# board1.net
KiCad netlist of a schematic drawn in EAGLE
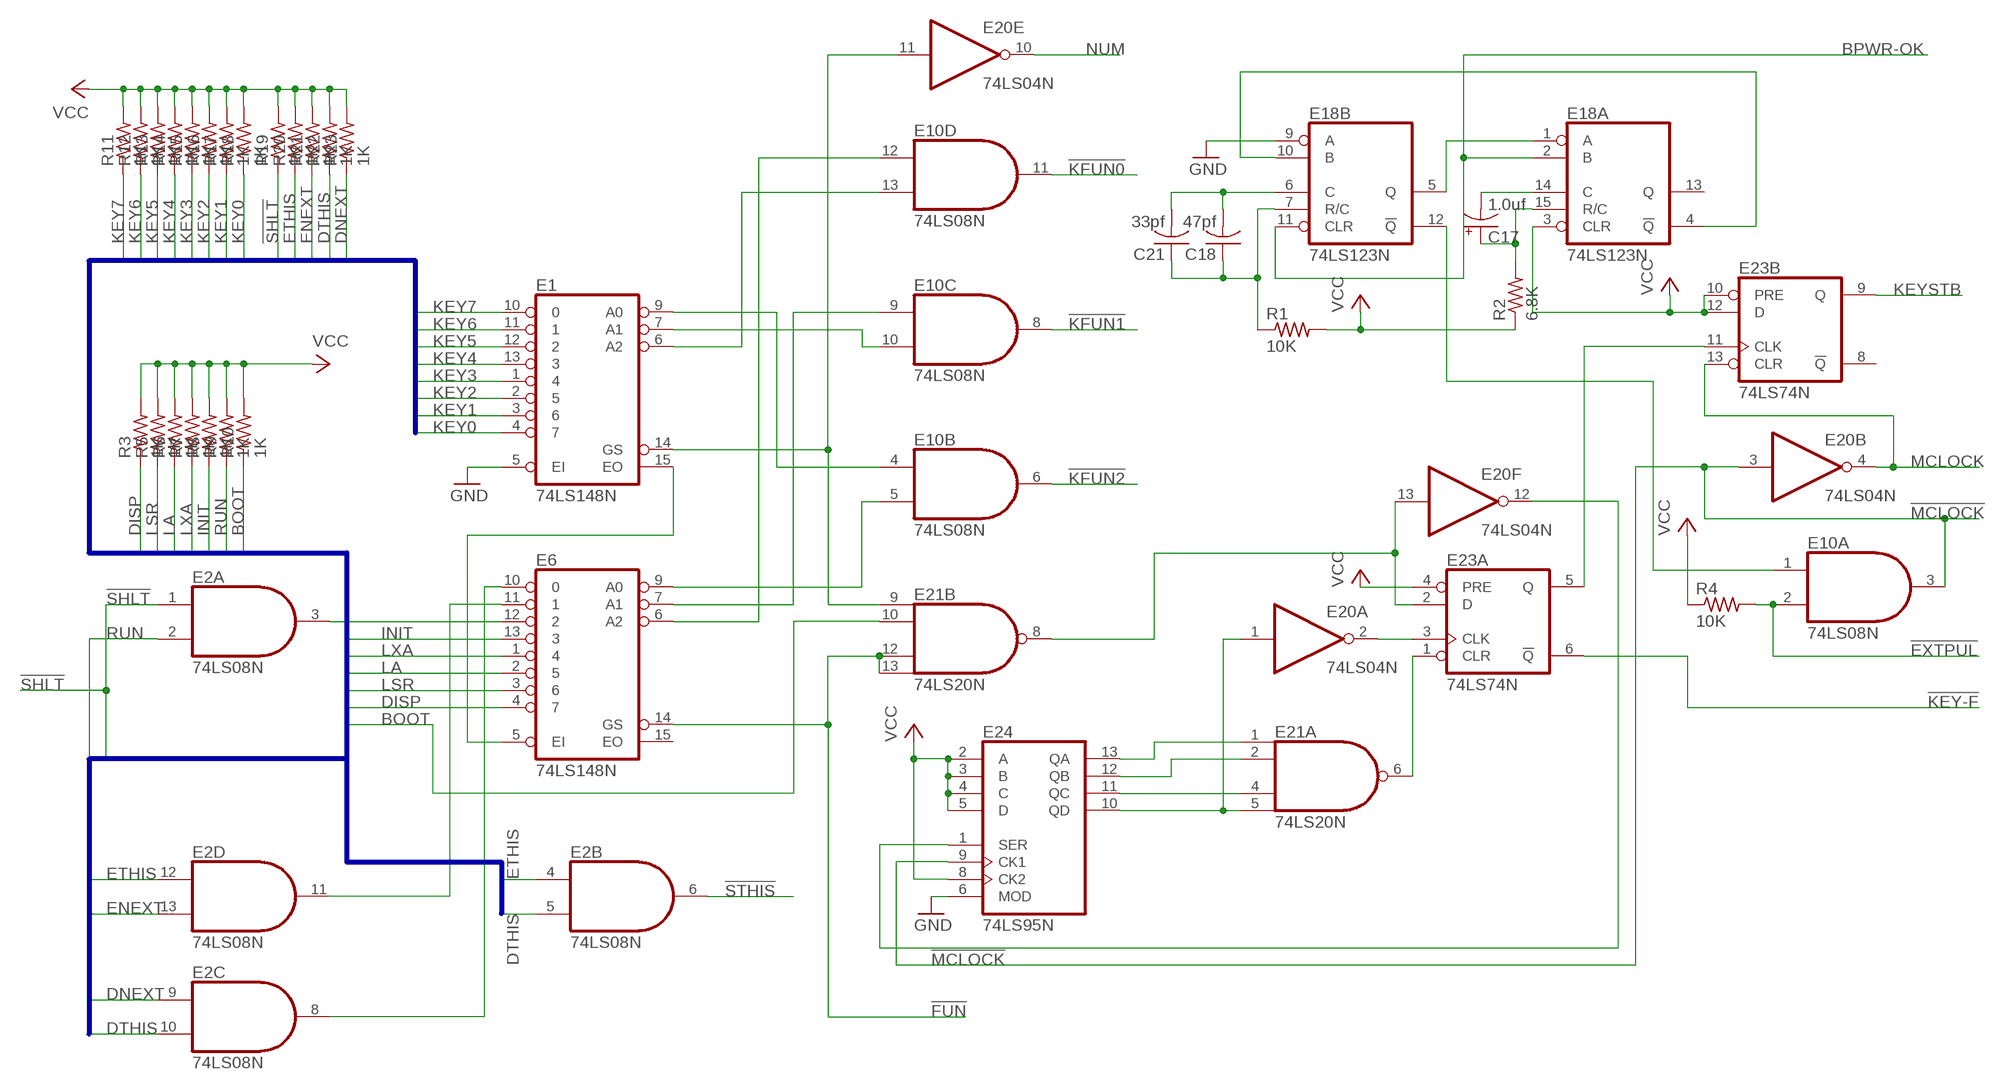
[diagram p0: schematic, sheet 1]
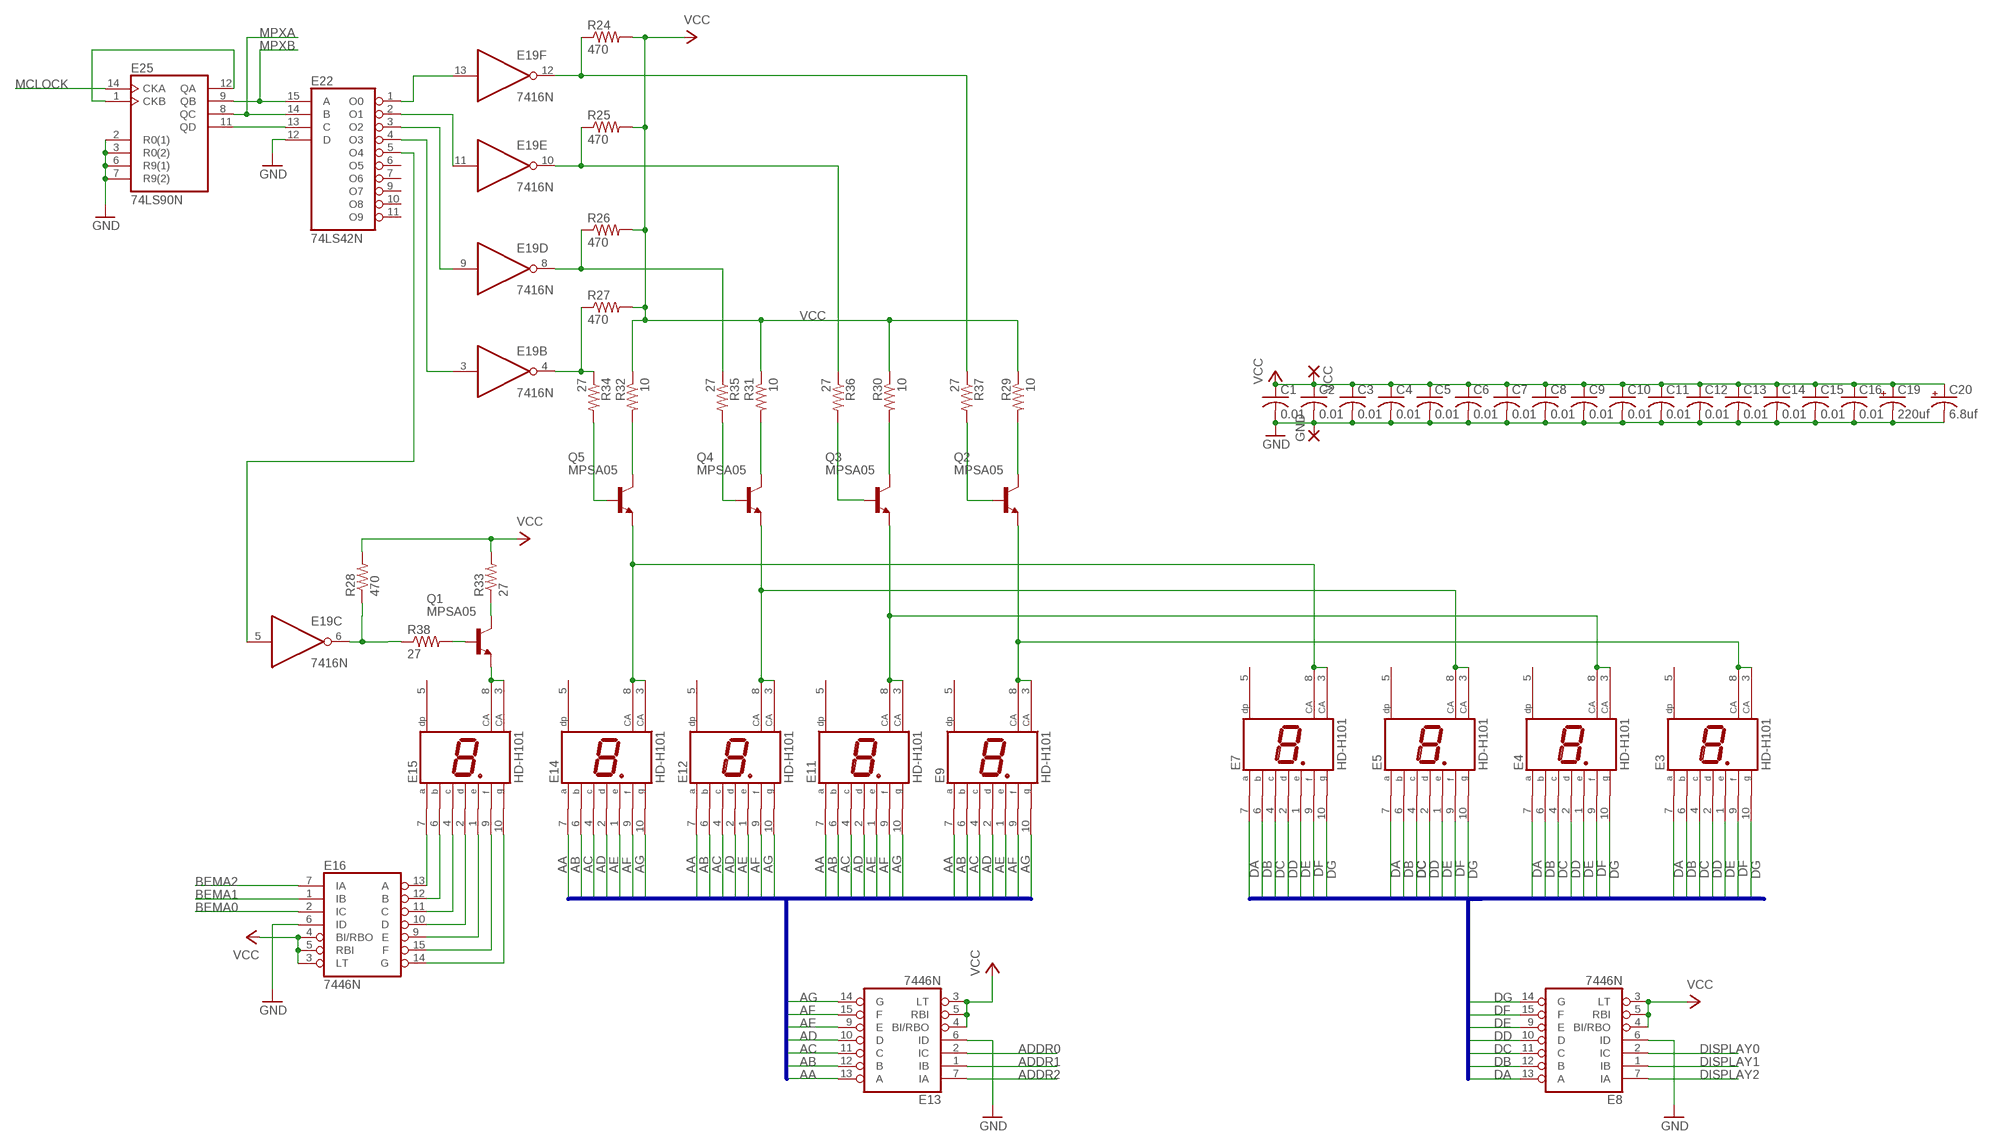
[diagram p1: schematic, sheet 2]
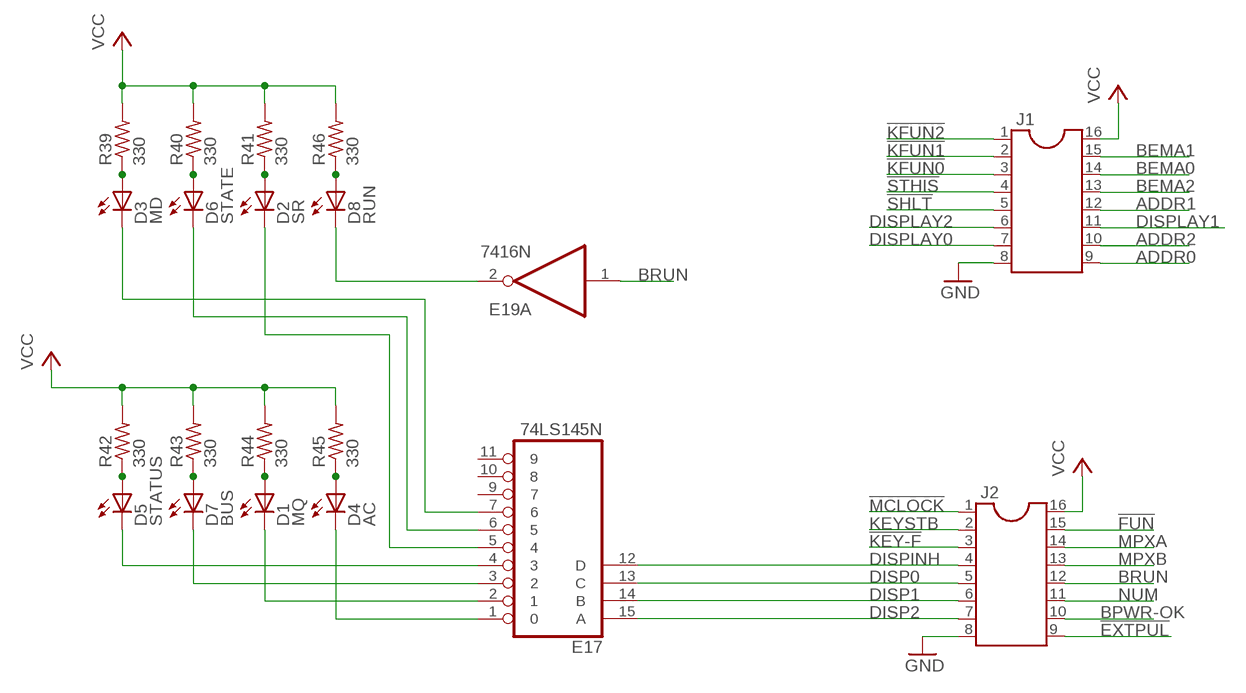
[diagram p2: schematic, sheet 3]
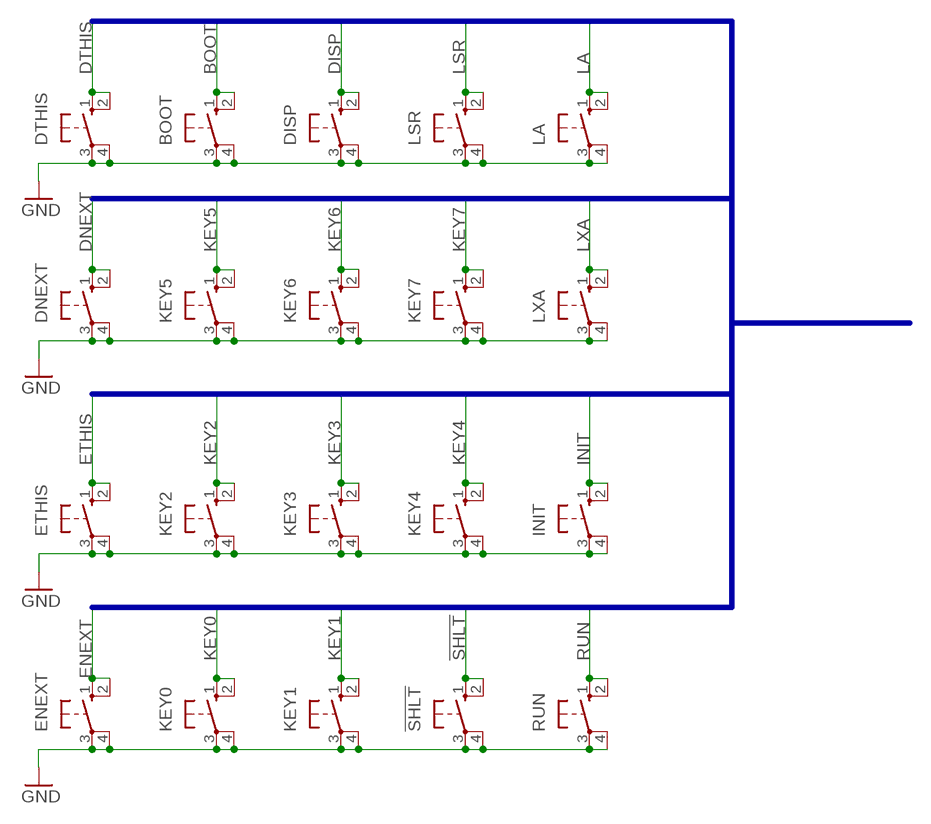
[diagram p3: schematic, sheet 4]

(export (version "E")
  (design (tool "Eeschema 10.0.6"))
  (components
    (comp (ref "C17")
      (value "1.0uf")
      (footprint "eagle-import:E15-5")
      (libsource (lib "eagle-import") (part "CPOL-USE15-5AXIAL"))
    )
    (comp (ref "C18")
      (value "47pf")
      (footprint "eagle-import:C050-025X075")
      (libsource (lib "eagle-import") (part "C-US050-025X075"))
    )
    (comp (ref "C21")
      (value "33pf")
      (footprint "eagle-import:C050-025X075")
      (libsource (lib "eagle-import") (part "C-US050-025X075"))
    )
    (comp (ref "E1")
      (value "74LS148N")
      (footprint "eagle-import:DIL16")
      (libsource (lib "eagle-import") (part "74148NLS"))
    )
    (comp (ref "E2")
      (value "74LS08N")
      (footprint "eagle-import:DIL14")
      (libsource (lib "eagle-import") (part "7408NLS"))
    )
    (comp (ref "E6")
      (value "74LS148N")
      (footprint "eagle-import:DIL16")
      (libsource (lib "eagle-import") (part "74148NLS"))
    )
    (comp (ref "E10")
      (value "74LS08N")
      (footprint "eagle-import:DIL14")
      (libsource (lib "eagle-import") (part "7408NLS"))
    )
    (comp (ref "E18")
      (value "74LS123N")
      (footprint "eagle-import:DIL16")
      (libsource (lib "eagle-import") (part "74123NLS"))
    )
    (comp (ref "E20")
      (value "74LS04N")
      (footprint "eagle-import:DIL14")
      (libsource (lib "eagle-import") (part "7404NLS"))
    )
    (comp (ref "E21")
      (value "74LS20N")
      (footprint "eagle-import:DIL14")
      (libsource (lib "eagle-import") (part "7420NLS"))
    )
    (comp (ref "E23")
      (value "74LS74N")
      (footprint "eagle-import:DIL14")
      (libsource (lib "eagle-import") (part "7474NLS"))
    )
    (comp (ref "E24")
      (value "74LS95N")
      (footprint "eagle-import:DIL14")
      (libsource (lib "eagle-import") (part "7495NLS"))
    )
    (comp (ref "R1")
      (value "10K")
      (footprint "eagle-import:0207_10")
      (libsource (lib "eagle-import") (part "R-US_0207/10"))
    )
    (comp (ref "R2")
      (value "6.8K")
      (footprint "eagle-import:0207_10")
      (libsource (lib "eagle-import") (part "R-US_0207/10"))
    )
    (comp (ref "R3")
      (value "1K")
      (footprint "eagle-import:0207_10")
      (libsource (lib "eagle-import") (part "R-US_0207/10"))
    )
    (comp (ref "R4")
      (value "10K")
      (footprint "eagle-import:0207_10")
      (libsource (lib "eagle-import") (part "R-US_0207/10"))
    )
    (comp (ref "R5")
      (value "1K")
      (footprint "eagle-import:0207_10")
      (libsource (lib "eagle-import") (part "R-US_0207/10"))
    )
    (comp (ref "R6")
      (value "1K")
      (footprint "eagle-import:0207_10")
      (libsource (lib "eagle-import") (part "R-US_0207/10"))
    )
    (comp (ref "R7")
      (value "1K")
      (footprint "eagle-import:0207_10")
      (libsource (lib "eagle-import") (part "R-US_0207/10"))
    )
    (comp (ref "R8")
      (value "1K")
      (footprint "eagle-import:0207_10")
      (libsource (lib "eagle-import") (part "R-US_0207/10"))
    )
    (comp (ref "R9")
      (value "1K")
      (footprint "eagle-import:0207_10")
      (libsource (lib "eagle-import") (part "R-US_0207/10"))
    )
    (comp (ref "R10")
      (value "1K")
      (footprint "eagle-import:0207_10")
      (libsource (lib "eagle-import") (part "R-US_0207/10"))
    )
    (comp (ref "R11")
      (value "1K")
      (footprint "eagle-import:0207_10")
      (libsource (lib "eagle-import") (part "R-US_0207/10"))
    )
    (comp (ref "R12")
      (value "1K")
      (footprint "eagle-import:0207_10")
      (libsource (lib "eagle-import") (part "R-US_0207/10"))
    )
    (comp (ref "R13")
      (value "1K")
      (footprint "eagle-import:0207_10")
      (libsource (lib "eagle-import") (part "R-US_0207/10"))
    )
    (comp (ref "R14")
      (value "1K")
      (footprint "eagle-import:0207_10")
      (libsource (lib "eagle-import") (part "R-US_0207/10"))
    )
    (comp (ref "R15")
      (value "1K")
      (footprint "eagle-import:0207_10")
      (libsource (lib "eagle-import") (part "R-US_0207/10"))
    )
    (comp (ref "R16")
      (value "1K")
      (footprint "eagle-import:0207_10")
      (libsource (lib "eagle-import") (part "R-US_0207/10"))
    )
    (comp (ref "R17")
      (value "1K")
      (footprint "eagle-import:0207_10")
      (libsource (lib "eagle-import") (part "R-US_0207/10"))
    )
    (comp (ref "R18")
      (value "1K")
      (footprint "eagle-import:0207_10")
      (libsource (lib "eagle-import") (part "R-US_0207/10"))
    )
    (comp (ref "R19")
      (value "1K")
      (footprint "eagle-import:0207_10")
      (libsource (lib "eagle-import") (part "R-US_0207/10"))
    )
    (comp (ref "R20")
      (value "1K")
      (footprint "eagle-import:0207_10")
      (libsource (lib "eagle-import") (part "R-US_0207/10"))
    )
    (comp (ref "R21")
      (value "1K")
      (footprint "eagle-import:0207_10")
      (libsource (lib "eagle-import") (part "R-US_0207/10"))
    )
    (comp (ref "R22")
      (value "1K")
      (footprint "eagle-import:0207_10")
      (libsource (lib "eagle-import") (part "R-US_0207/10"))
    )
    (comp (ref "R23")
      (value "1K")
      (footprint "eagle-import:0207_10")
      (libsource (lib "eagle-import") (part "R-US_0207/10"))
    )
    (comp (ref "C1")
      (value "0.01")
      (footprint "eagle-import:C050-025X075")
      (libsource (lib "eagle-import") (part "C-US050-025X075"))
    )
    (comp (ref "C2")
      (value "0.01")
      (footprint "eagle-import:C050-025X075")
      (libsource (lib "eagle-import") (part "C-US050-025X075"))
    )
    (comp (ref "C3")
      (value "0.01")
      (footprint "eagle-import:C050-025X075")
      (libsource (lib "eagle-import") (part "C-US050-025X075"))
    )
    (comp (ref "C4")
      (value "0.01")
      (footprint "eagle-import:C050-025X075")
      (libsource (lib "eagle-import") (part "C-US050-025X075"))
    )
    (comp (ref "C5")
      (value "0.01")
      (footprint "eagle-import:C050-025X075")
      (libsource (lib "eagle-import") (part "C-US050-025X075"))
    )
    (comp (ref "C6")
      (value "0.01")
      (footprint "eagle-import:C050-025X075")
      (libsource (lib "eagle-import") (part "C-US050-025X075"))
    )
    (comp (ref "C7")
      (value "0.01")
      (footprint "eagle-import:C050-025X075")
      (libsource (lib "eagle-import") (part "C-US050-025X075"))
    )
    (comp (ref "C8")
      (value "0.01")
      (footprint "eagle-import:C050-025X075")
      (libsource (lib "eagle-import") (part "C-US050-025X075"))
    )
    (comp (ref "C9")
      (value "0.01")
      (footprint "eagle-import:C050-025X075")
      (libsource (lib "eagle-import") (part "C-US050-025X075"))
    )
    (comp (ref "C10")
      (value "0.01")
      (footprint "eagle-import:C050-025X075")
      (libsource (lib "eagle-import") (part "C-US050-025X075"))
    )
    (comp (ref "C11")
      (value "0.01")
      (footprint "eagle-import:C050-025X075")
      (libsource (lib "eagle-import") (part "C-US050-025X075"))
    )
    (comp (ref "C12")
      (value "0.01")
      (footprint "eagle-import:C050-025X075")
      (libsource (lib "eagle-import") (part "C-US050-025X075"))
    )
    (comp (ref "C13")
      (value "0.01")
      (footprint "eagle-import:C050-025X075")
      (libsource (lib "eagle-import") (part "C-US050-025X075"))
    )
    (comp (ref "C14")
      (value "0.01")
      (footprint "eagle-import:C050-025X075")
      (libsource (lib "eagle-import") (part "C-US050-025X075"))
    )
    (comp (ref "C15")
      (value "0.01")
      (footprint "eagle-import:C050-025X075")
      (libsource (lib "eagle-import") (part "C-US050-025X075"))
    )
    (comp (ref "C16")
      (value "0.01")
      (footprint "eagle-import:C050-025X075")
      (libsource (lib "eagle-import") (part "C-US050-025X075"))
    )
    (comp (ref "C19")
      (value "220uf")
      (footprint "eagle-import:E22-6")
      (libsource (lib "eagle-import") (part "CPOL-USE22-6AXIAL"))
    )
    (comp (ref "C20")
      (value "6.8uf")
      (footprint "eagle-import:E22-6")
      (libsource (lib "eagle-import") (part "CPOL-USE22-6AXIAL"))
    )
    (comp (ref "E3")
      (value "HD-H101")
      (footprint "eagle-import:HDSP-M")
      (libsource (lib "eagle-import") (part "HD-H101"))
    )
    (comp (ref "E4")
      (value "HD-H101")
      (footprint "eagle-import:HDSP-M")
      (libsource (lib "eagle-import") (part "HD-H101"))
    )
    (comp (ref "E5")
      (value "HD-H101")
      (footprint "eagle-import:HDSP-M")
      (libsource (lib "eagle-import") (part "HD-H101"))
    )
    (comp (ref "E7")
      (value "HD-H101")
      (footprint "eagle-import:HDSP-M")
      (libsource (lib "eagle-import") (part "HD-H101"))
    )
    (comp (ref "E8")
      (value "7446N")
      (footprint "eagle-import:DIL16")
      (libsource (lib "eagle-import") (part "7446N"))
    )
    (comp (ref "E9")
      (value "HD-H101")
      (footprint "eagle-import:HDSP-M")
      (libsource (lib "eagle-import") (part "HD-H101"))
    )
    (comp (ref "E11")
      (value "HD-H101")
      (footprint "eagle-import:HDSP-M")
      (libsource (lib "eagle-import") (part "HD-H101"))
    )
    (comp (ref "E12")
      (value "HD-H101")
      (footprint "eagle-import:HDSP-M")
      (libsource (lib "eagle-import") (part "HD-H101"))
    )
    (comp (ref "E13")
      (value "7446N")
      (footprint "eagle-import:DIL16")
      (libsource (lib "eagle-import") (part "7446N"))
    )
    (comp (ref "E14")
      (value "HD-H101")
      (footprint "eagle-import:HDSP-M")
      (libsource (lib "eagle-import") (part "HD-H101"))
    )
    (comp (ref "E15")
      (value "HD-H101")
      (footprint "eagle-import:HDSP-M")
      (libsource (lib "eagle-import") (part "HD-H101"))
    )
    (comp (ref "E16")
      (value "7446N")
      (footprint "eagle-import:DIL16")
      (libsource (lib "eagle-import") (part "7446N"))
    )
    (comp (ref "E19")
      (value "7416N")
      (footprint "eagle-import:DIL14")
      (libsource (lib "eagle-import") (part "7416N"))
    )
    (comp (ref "E22")
      (value "74LS42N")
      (footprint "eagle-import:DIL16")
      (libsource (lib "eagle-import") (part "7442NLS"))
    )
    (comp (ref "E25")
      (value "74LS90N")
      (footprint "eagle-import:DIL14")
      (libsource (lib "eagle-import") (part "7490NLS"))
    )
    (comp (ref "GND")
      (value "3,81/1,4")
      (footprint "eagle-import:3,81_1,4")
      (libsource (lib "eagle-import") (part "3,81/1,4"))
    )
    (comp (ref "Q1")
      (value "MPSA05")
      (footprint "eagle-import:TO18")
      (libsource (lib "eagle-import") (part "2N2222A"))
    )
    (comp (ref "Q2")
      (value "MPSA05")
      (footprint "eagle-import:TO18")
      (libsource (lib "eagle-import") (part "2N2222A"))
    )
    (comp (ref "Q3")
      (value "MPSA05")
      (footprint "eagle-import:TO18")
      (libsource (lib "eagle-import") (part "2N2222A"))
    )
    (comp (ref "Q4")
      (value "MPSA05")
      (footprint "eagle-import:TO18")
      (libsource (lib "eagle-import") (part "2N2222A"))
    )
    (comp (ref "Q5")
      (value "MPSA05")
      (footprint "eagle-import:TO18")
      (libsource (lib "eagle-import") (part "2N2222A"))
    )
    (comp (ref "R24")
      (value "470")
      (footprint "eagle-import:0207_10")
      (libsource (lib "eagle-import") (part "R-US_0207/10"))
    )
    (comp (ref "R25")
      (value "470")
      (footprint "eagle-import:0207_10")
      (libsource (lib "eagle-import") (part "R-US_0207/10"))
    )
    (comp (ref "R26")
      (value "470")
      (footprint "eagle-import:0207_10")
      (libsource (lib "eagle-import") (part "R-US_0207/10"))
    )
    (comp (ref "R27")
      (value "470")
      (footprint "eagle-import:0207_10")
      (libsource (lib "eagle-import") (part "R-US_0207/10"))
    )
    (comp (ref "R28")
      (value "470")
      (footprint "eagle-import:0207_10")
      (libsource (lib "eagle-import") (part "R-US_0207/10"))
    )
    (comp (ref "R29")
      (value "10")
      (footprint "eagle-import:0207_10")
      (libsource (lib "eagle-import") (part "R-US_0207/10"))
    )
    (comp (ref "R30")
      (value "10")
      (footprint "eagle-import:0207_10")
      (libsource (lib "eagle-import") (part "R-US_0207/10"))
    )
    (comp (ref "R31")
      (value "10")
      (footprint "eagle-import:0207_10")
      (libsource (lib "eagle-import") (part "R-US_0207/10"))
    )
    (comp (ref "R32")
      (value "10")
      (footprint "eagle-import:0207_10")
      (libsource (lib "eagle-import") (part "R-US_0207/10"))
    )
    (comp (ref "R33")
      (value "27")
      (footprint "eagle-import:0207_10")
      (libsource (lib "eagle-import") (part "R-US_0207/10"))
    )
    (comp (ref "R34")
      (value "27")
      (footprint "eagle-import:0207_10")
      (libsource (lib "eagle-import") (part "R-US_0207/10"))
    )
    (comp (ref "R35")
      (value "27")
      (footprint "eagle-import:0207_10")
      (libsource (lib "eagle-import") (part "R-US_0207/10"))
    )
    (comp (ref "R36")
      (value "27")
      (footprint "eagle-import:0207_10")
      (libsource (lib "eagle-import") (part "R-US_0207/10"))
    )
    (comp (ref "R37")
      (value "27")
      (footprint "eagle-import:0207_10")
      (libsource (lib "eagle-import") (part "R-US_0207/10"))
    )
    (comp (ref "R38")
      (value "27")
      (footprint "eagle-import:0207_10")
      (libsource (lib "eagle-import") (part "R-US_0207/10"))
    )
    (comp (ref "VCC")
      (value "3,81/1,4")
      (footprint "eagle-import:3,81_1,4")
      (libsource (lib "eagle-import") (part "3,81/1,4"))
    )
    (comp (ref "D1")
      (value "MQ")
      (footprint "eagle-import:LED5MM")
      (libsource (lib "eagle-import") (part "LED5MM"))
    )
    (comp (ref "D2")
      (value "SR")
      (footprint "eagle-import:LED5MM")
      (libsource (lib "eagle-import") (part "LED5MM"))
    )
    (comp (ref "D3")
      (value "MD")
      (footprint "eagle-import:LED5MM")
      (libsource (lib "eagle-import") (part "LED5MM"))
    )
    (comp (ref "D4")
      (value "AC")
      (footprint "eagle-import:LED5MM")
      (libsource (lib "eagle-import") (part "LED5MM"))
    )
    (comp (ref "D5")
      (value "STATUS")
      (footprint "eagle-import:LED5MM")
      (libsource (lib "eagle-import") (part "LED5MM"))
    )
    (comp (ref "D6")
      (value "STATE")
      (footprint "eagle-import:LED5MM")
      (libsource (lib "eagle-import") (part "LED5MM"))
    )
    (comp (ref "D7")
      (value "BUS")
      (footprint "eagle-import:LED5MM")
      (libsource (lib "eagle-import") (part "LED5MM"))
    )
    (comp (ref "D8")
      (value "RUN")
      (footprint "eagle-import:LED5MM")
      (libsource (lib "eagle-import") (part "LED5MM"))
    )
    (comp (ref "E17")
      (value "74LS145N")
      (footprint "eagle-import:DIL16")
      (libsource (lib "eagle-import") (part "74145NLS"))
    )
    (comp (ref "J1")
      (value "DIL16S")
      (footprint "eagle-import:SOCKET-16")
      (libsource (lib "eagle-import") (part "DIL16S"))
    )
    (comp (ref "J2")
      (value "DIL16S")
      (footprint "eagle-import:SOCKET-16")
      (libsource (lib "eagle-import") (part "DIL16S"))
    )
    (comp (ref "R39")
      (value "330")
      (footprint "eagle-import:0207_10")
      (libsource (lib "eagle-import") (part "R-US_0207/10"))
    )
    (comp (ref "R40")
      (value "330")
      (footprint "eagle-import:0207_10")
      (libsource (lib "eagle-import") (part "R-US_0207/10"))
    )
    (comp (ref "R41")
      (value "330")
      (footprint "eagle-import:0207_10")
      (libsource (lib "eagle-import") (part "R-US_0207/10"))
    )
    (comp (ref "R42")
      (value "330")
      (footprint "eagle-import:0207_10")
      (libsource (lib "eagle-import") (part "R-US_0207/10"))
    )
    (comp (ref "R43")
      (value "330")
      (footprint "eagle-import:0207_10")
      (libsource (lib "eagle-import") (part "R-US_0207/10"))
    )
    (comp (ref "R44")
      (value "330")
      (footprint "eagle-import:0207_10")
      (libsource (lib "eagle-import") (part "R-US_0207/10"))
    )
    (comp (ref "R45")
      (value "330")
      (footprint "eagle-import:0207_10")
      (libsource (lib "eagle-import") (part "R-US_0207/10"))
    )
    (comp (ref "R46")
      (value "330")
      (footprint "eagle-import:0207_10")
      (libsource (lib "eagle-import") (part "R-US_0207/10"))
    )
    (comp (ref "!SHLT")
      (value "40-XX")
      (footprint "eagle-import:B3F-40XX")
      (fields (field (name "MF") "OMRON COMPONENTS USA") (field (name "MPN") "B3F-4000"))
      (libsource (lib "eagle-import") (part "40-XX"))
    )
    (comp (ref "BOOT")
      (value "40-XX")
      (footprint "eagle-import:B3F-40XX")
      (fields (field (name "MF") "OMRON COMPONENTS USA") (field (name "MPN") "B3F-4000"))
      (libsource (lib "eagle-import") (part "40-XX"))
    )
    (comp (ref "DISP")
      (value "40-XX")
      (footprint "eagle-import:B3F-40XX")
      (fields (field (name "MF") "OMRON COMPONENTS USA") (field (name "MPN") "B3F-4000"))
      (libsource (lib "eagle-import") (part "40-XX"))
    )
    (comp (ref "DNEXT")
      (value "40-XX")
      (footprint "eagle-import:B3F-40XX")
      (fields (field (name "MF") "OMRON COMPONENTS USA") (field (name "MPN") "B3F-4000"))
      (libsource (lib "eagle-import") (part "40-XX"))
    )
    (comp (ref "DTHIS")
      (value "40-XX")
      (footprint "eagle-import:B3F-40XX")
      (fields (field (name "MF") "OMRON COMPONENTS USA") (field (name "MPN") "B3F-4000"))
      (libsource (lib "eagle-import") (part "40-XX"))
    )
    (comp (ref "ENEXT")
      (value "40-XX")
      (footprint "eagle-import:B3F-40XX")
      (fields (field (name "MF") "OMRON COMPONENTS USA") (field (name "MPN") "B3F-4000"))
      (libsource (lib "eagle-import") (part "40-XX"))
    )
    (comp (ref "ETHIS")
      (value "40-XX")
      (footprint "eagle-import:B3F-40XX")
      (fields (field (name "MF") "OMRON COMPONENTS USA") (field (name "MPN") "B3F-4000"))
      (libsource (lib "eagle-import") (part "40-XX"))
    )
    (comp (ref "INIT")
      (value "40-XX")
      (footprint "eagle-import:B3F-40XX")
      (fields (field (name "MF") "OMRON COMPONENTS USA") (field (name "MPN") "B3F-4000"))
      (libsource (lib "eagle-import") (part "40-XX"))
    )
    (comp (ref "KEY0")
      (value "40-XX")
      (footprint "eagle-import:B3F-40XX")
      (fields (field (name "MF") "OMRON COMPONENTS USA") (field (name "MPN") "B3F-4000"))
      (libsource (lib "eagle-import") (part "40-XX"))
    )
    (comp (ref "KEY1")
      (value "40-XX")
      (footprint "eagle-import:B3F-40XX")
      (fields (field (name "MF") "OMRON COMPONENTS USA") (field (name "MPN") "B3F-4000"))
      (libsource (lib "eagle-import") (part "40-XX"))
    )
    (comp (ref "KEY2")
      (value "40-XX")
      (footprint "eagle-import:B3F-40XX")
      (fields (field (name "MF") "OMRON COMPONENTS USA") (field (name "MPN") "B3F-4000"))
      (libsource (lib "eagle-import") (part "40-XX"))
    )
    (comp (ref "KEY3")
      (value "40-XX")
      (footprint "eagle-import:B3F-40XX")
      (fields (field (name "MF") "OMRON COMPONENTS USA") (field (name "MPN") "B3F-4000"))
      (libsource (lib "eagle-import") (part "40-XX"))
    )
    (comp (ref "KEY4")
      (value "40-XX")
      (footprint "eagle-import:B3F-40XX")
      (fields (field (name "MF") "OMRON COMPONENTS USA") (field (name "MPN") "B3F-4000"))
      (libsource (lib "eagle-import") (part "40-XX"))
    )
    (comp (ref "KEY5")
      (value "40-XX")
      (footprint "eagle-import:B3F-40XX")
      (fields (field (name "MF") "OMRON COMPONENTS USA") (field (name "MPN") "B3F-4000"))
      (libsource (lib "eagle-import") (part "40-XX"))
    )
    (comp (ref "KEY6")
      (value "40-XX")
      (footprint "eagle-import:B3F-40XX")
      (fields (field (name "MF") "OMRON COMPONENTS USA") (field (name "MPN") "B3F-4000"))
      (libsource (lib "eagle-import") (part "40-XX"))
    )
    (comp (ref "KEY7")
      (value "40-XX")
      (footprint "eagle-import:B3F-40XX")
      (fields (field (name "MF") "OMRON COMPONENTS USA") (field (name "MPN") "B3F-4000"))
      (libsource (lib "eagle-import") (part "40-XX"))
    )
    (comp (ref "LA")
      (value "40-XX")
      (footprint "eagle-import:B3F-40XX")
      (fields (field (name "MF") "OMRON COMPONENTS USA") (field (name "MPN") "B3F-4000"))
      (libsource (lib "eagle-import") (part "40-XX"))
    )
    (comp (ref "LSR")
      (value "40-XX")
      (footprint "eagle-import:B3F-40XX")
      (fields (field (name "MF") "OMRON COMPONENTS USA") (field (name "MPN") "B3F-4000"))
      (libsource (lib "eagle-import") (part "40-XX"))
    )
    (comp (ref "LXA")
      (value "40-XX")
      (footprint "eagle-import:B3F-40XX")
      (fields (field (name "MF") "OMRON COMPONENTS USA") (field (name "MPN") "B3F-4000"))
      (libsource (lib "eagle-import") (part "40-XX"))
    )
    (comp (ref "RUN")
      (value "40-XX")
      (footprint "eagle-import:B3F-40XX")
      (fields (field (name "MF") "OMRON COMPONENTS USA") (field (name "MPN") "B3F-4000"))
      (libsource (lib "eagle-import") (part "40-XX"))
    )
  )
  (nets
    (net (code "1") (name "AA") (class "Default")
      (node (ref "E11") (pin "7") (pinfunction "A_7") (pintype "passive"))
      (node (ref "E12") (pin "7") (pinfunction "A_7") (pintype "passive"))
      (node (ref "E13") (pin "13") (pinfunction "A_13") (pintype "open_collector"))
      (node (ref "E14") (pin "7") (pinfunction "A_7") (pintype "passive"))
      (node (ref "E9") (pin "7") (pinfunction "A_7") (pintype "passive"))
    )
    (net (code "2") (name "AB") (class "Default")
      (node (ref "E11") (pin "6") (pinfunction "B_6") (pintype "passive"))
      (node (ref "E12") (pin "6") (pinfunction "B_6") (pintype "passive"))
      (node (ref "E13") (pin "12") (pinfunction "B_12") (pintype "open_collector"))
      (node (ref "E14") (pin "6") (pinfunction "B_6") (pintype "passive"))
      (node (ref "E9") (pin "6") (pinfunction "B_6") (pintype "passive"))
    )
    (net (code "3") (name "AC") (class "Default")
      (node (ref "E11") (pin "4") (pinfunction "C_4") (pintype "passive"))
      (node (ref "E12") (pin "4") (pinfunction "C_4") (pintype "passive"))
      (node (ref "E13") (pin "11") (pinfunction "C_11") (pintype "open_collector"))
      (node (ref "E14") (pin "4") (pinfunction "C_4") (pintype "passive"))
      (node (ref "E9") (pin "4") (pinfunction "C_4") (pintype "passive"))
    )
    (net (code "4") (name "AD") (class "Default")
      (node (ref "E11") (pin "2") (pinfunction "D_2") (pintype "passive"))
      (node (ref "E12") (pin "2") (pinfunction "D_2") (pintype "passive"))
      (node (ref "E13") (pin "10") (pinfunction "D_10") (pintype "open_collector"))
      (node (ref "E14") (pin "2") (pinfunction "D_2") (pintype "passive"))
      (node (ref "E9") (pin "2") (pinfunction "D_2") (pintype "passive"))
    )
    (net (code "5") (name "ADDR0") (class "Default")
      (node (ref "E13") (pin "2") (pinfunction "IC_2") (pintype "input"))
      (node (ref "J1") (pin "9") (pinfunction "9_9") (pintype "passive"))
    )
    (net (code "6") (name "ADDR1") (class "Default")
      (node (ref "E13") (pin "1") (pinfunction "IB_1") (pintype "input"))
      (node (ref "J1") (pin "12") (pinfunction "12_12") (pintype "passive"))
    )
    (net (code "7") (name "ADDR2") (class "Default")
      (node (ref "E13") (pin "7") (pinfunction "IA_7") (pintype "input"))
      (node (ref "J1") (pin "10") (pinfunction "10_10") (pintype "passive"))
    )
    (net (code "8") (name "AE") (class "Default")
      (node (ref "E11") (pin "1") (pinfunction "E_1") (pintype "passive"))
      (node (ref "E12") (pin "1") (pinfunction "E_1") (pintype "passive"))
      (node (ref "E13") (pin "9") (pinfunction "E_9") (pintype "open_collector"))
      (node (ref "E14") (pin "1") (pinfunction "E_1") (pintype "passive"))
      (node (ref "E9") (pin "1") (pinfunction "E_1") (pintype "passive"))
    )
    (net (code "9") (name "AF") (class "Default")
      (node (ref "E11") (pin "9") (pinfunction "F_9") (pintype "passive"))
      (node (ref "E12") (pin "9") (pinfunction "F_9") (pintype "passive"))
      (node (ref "E13") (pin "15") (pinfunction "F_15") (pintype "open_collector"))
      (node (ref "E14") (pin "9") (pinfunction "F_9") (pintype "passive"))
      (node (ref "E9") (pin "9") (pinfunction "F_9") (pintype "passive"))
    )
    (net (code "10") (name "AG") (class "Default")
      (node (ref "E11") (pin "10") (pinfunction "G_10") (pintype "passive"))
      (node (ref "E12") (pin "10") (pinfunction "G_10") (pintype "passive"))
      (node (ref "E13") (pin "14") (pinfunction "G_14") (pintype "open_collector"))
      (node (ref "E14") (pin "10") (pinfunction "G_10") (pintype "passive"))
      (node (ref "E9") (pin "10") (pinfunction "G_10") (pintype "passive"))
    )
    (net (code "11") (name "BEMA0") (class "Default")
      (node (ref "E16") (pin "2") (pinfunction "IC_2") (pintype "input"))
      (node (ref "J1") (pin "14") (pinfunction "14_14") (pintype "passive"))
    )
    (net (code "12") (name "BEMA1") (class "Default")
      (node (ref "E16") (pin "1") (pinfunction "IB_1") (pintype "input"))
      (node (ref "J1") (pin "15") (pinfunction "15_15") (pintype "passive"))
    )
    (net (code "13") (name "BEMA2") (class "Default")
      (node (ref "E16") (pin "7") (pinfunction "IA_7") (pintype "input"))
      (node (ref "J1") (pin "13") (pinfunction "13_13") (pintype "passive"))
    )
    (net (code "14") (name "BOOT") (class "Default")
      (node (ref "BOOT") (pin "1") (pinfunction "S_1") (pintype "passive"))
      (node (ref "BOOT") (pin "2") (pinfunction "S1_2") (pintype "passive"))
      (node (ref "E21") (pin "10") (pinfunction "I1_10") (pintype "input"))
      (node (ref "R10") (pin "1") (pinfunction "1_1") (pintype "passive"))
    )
    (net (code "15") (name "BPWR-OK") (class "Default")
      (node (ref "E18") (pin "11") (pinfunction "CLR_11") (pintype "input"))
      (node (ref "E18") (pin "2") (pinfunction "B_2") (pintype "input"))
      (node (ref "J2") (pin "10") (pinfunction "10_10") (pintype "passive"))
    )
    (net (code "16") (name "BRUN") (class "Default")
      (node (ref "E19") (pin "1") (pinfunction "I_1") (pintype "input"))
      (node (ref "J2") (pin "12") (pinfunction "12_12") (pintype "passive"))
    )
    (net (code "17") (name "DA") (class "Default")
      (node (ref "E3") (pin "7") (pinfunction "A_7") (pintype "passive"))
      (node (ref "E4") (pin "7") (pinfunction "A_7") (pintype "passive"))
      (node (ref "E5") (pin "7") (pinfunction "A_7") (pintype "passive"))
      (node (ref "E7") (pin "7") (pinfunction "A_7") (pintype "passive"))
      (node (ref "E8") (pin "13") (pinfunction "A_13") (pintype "open_collector"))
    )
    (net (code "18") (name "DB") (class "Default")
      (node (ref "E3") (pin "6") (pinfunction "B_6") (pintype "passive"))
      (node (ref "E4") (pin "6") (pinfunction "B_6") (pintype "passive"))
      (node (ref "E5") (pin "6") (pinfunction "B_6") (pintype "passive"))
      (node (ref "E7") (pin "6") (pinfunction "B_6") (pintype "passive"))
      (node (ref "E8") (pin "12") (pinfunction "B_12") (pintype "open_collector"))
    )
    (net (code "19") (name "DC") (class "Default")
      (node (ref "E3") (pin "4") (pinfunction "C_4") (pintype "passive"))
      (node (ref "E4") (pin "4") (pinfunction "C_4") (pintype "passive"))
      (node (ref "E5") (pin "4") (pinfunction "C_4") (pintype "passive"))
      (node (ref "E7") (pin "4") (pinfunction "C_4") (pintype "passive"))
      (node (ref "E8") (pin "11") (pinfunction "C_11") (pintype "open_collector"))
    )
    (net (code "20") (name "DD") (class "Default")
      (node (ref "E3") (pin "2") (pinfunction "D_2") (pintype "passive"))
      (node (ref "E4") (pin "2") (pinfunction "D_2") (pintype "passive"))
      (node (ref "E5") (pin "2") (pinfunction "D_2") (pintype "passive"))
      (node (ref "E7") (pin "2") (pinfunction "D_2") (pintype "passive"))
      (node (ref "E8") (pin "10") (pinfunction "D_10") (pintype "open_collector"))
    )
    (net (code "21") (name "DE") (class "Default")
      (node (ref "E3") (pin "1") (pinfunction "E_1") (pintype "passive"))
      (node (ref "E4") (pin "1") (pinfunction "E_1") (pintype "passive"))
      (node (ref "E5") (pin "1") (pinfunction "E_1") (pintype "passive"))
      (node (ref "E7") (pin "1") (pinfunction "E_1") (pintype "passive"))
      (node (ref "E8") (pin "9") (pinfunction "E_9") (pintype "open_collector"))
    )
    (net (code "22") (name "DF") (class "Default")
      (node (ref "E3") (pin "9") (pinfunction "F_9") (pintype "passive"))
      (node (ref "E4") (pin "9") (pinfunction "F_9") (pintype "passive"))
      (node (ref "E5") (pin "9") (pinfunction "F_9") (pintype "passive"))
      (node (ref "E7") (pin "9") (pinfunction "F_9") (pintype "passive"))
      (node (ref "E8") (pin "15") (pinfunction "F_15") (pintype "open_collector"))
    )
    (net (code "23") (name "DG") (class "Default")
      (node (ref "E3") (pin "10") (pinfunction "G_10") (pintype "passive"))
      (node (ref "E4") (pin "10") (pinfunction "G_10") (pintype "passive"))
      (node (ref "E5") (pin "10") (pinfunction "G_10") (pintype "passive"))
      (node (ref "E7") (pin "10") (pinfunction "G_10") (pintype "passive"))
      (node (ref "E8") (pin "14") (pinfunction "G_14") (pintype "open_collector"))
    )
    (net (code "24") (name "DISP") (class "Default")
      (node (ref "DISP") (pin "1") (pinfunction "S_1") (pintype "passive"))
      (node (ref "DISP") (pin "2") (pinfunction "S1_2") (pintype "passive"))
      (node (ref "E6") (pin "4") (pinfunction "7_4") (pintype "input"))
      (node (ref "R3") (pin "1") (pinfunction "1_1") (pintype "passive"))
    )
    (net (code "25") (name "DISP0") (class "Default")
      (node (ref "E17") (pin "13") (pinfunction "C_13") (pintype "input"))
      (node (ref "J2") (pin "5") (pinfunction "5_5") (pintype "passive"))
    )
    (net (code "26") (name "DISP1") (class "Default")
      (node (ref "E17") (pin "14") (pinfunction "B_14") (pintype "input"))
      (node (ref "J2") (pin "6") (pinfunction "6_6") (pintype "passive"))
    )
    (net (code "27") (name "DISP2") (class "Default")
      (node (ref "E17") (pin "15") (pinfunction "A_15") (pintype "input"))
      (node (ref "J2") (pin "7") (pinfunction "7_7") (pintype "passive"))
    )
    (net (code "28") (name "DISPINH") (class "Default")
      (node (ref "E17") (pin "12") (pinfunction "D_12") (pintype "input"))
      (node (ref "J2") (pin "4") (pinfunction "4_4") (pintype "passive"))
    )
    (net (code "29") (name "DISPLAY0") (class "Default")
      (node (ref "E8") (pin "2") (pinfunction "IC_2") (pintype "input"))
      (node (ref "J1") (pin "7") (pinfunction "7_7") (pintype "passive"))
    )
    (net (code "30") (name "DISPLAY1") (class "Default")
      (node (ref "E8") (pin "1") (pinfunction "IB_1") (pintype "input"))
      (node (ref "J1") (pin "11") (pinfunction "11_11") (pintype "passive"))
    )
    (net (code "31") (name "DISPLAY2") (class "Default")
      (node (ref "E8") (pin "7") (pinfunction "IA_7") (pintype "input"))
      (node (ref "J1") (pin "6") (pinfunction "6_6") (pintype "passive"))
    )
    (net (code "32") (name "DNEXT") (class "Default")
      (node (ref "DNEXT") (pin "1") (pinfunction "S_1") (pintype "passive"))
      (node (ref "DNEXT") (pin "2") (pinfunction "S1_2") (pintype "passive"))
      (node (ref "E2") (pin "9") (pinfunction "I0_9") (pintype "input"))
      (node (ref "R23") (pin "1") (pinfunction "1_1") (pintype "passive"))
    )
    (net (code "33") (name "DTHIS") (class "Default")
      (node (ref "DTHIS") (pin "1") (pinfunction "S_1") (pintype "passive"))
      (node (ref "DTHIS") (pin "2") (pinfunction "S1_2") (pintype "passive"))
      (node (ref "E2") (pin "10") (pinfunction "I1_10") (pintype "input"))
      (node (ref "E2") (pin "5") (pinfunction "I1_5") (pintype "input"))
      (node (ref "R22") (pin "1") (pinfunction "1_1") (pintype "passive"))
    )
    (net (code "34") (name "ENEXT") (class "Default")
      (node (ref "E2") (pin "13") (pinfunction "I1_13") (pintype "input"))
      (node (ref "ENEXT") (pin "1") (pinfunction "S_1") (pintype "passive"))
      (node (ref "ENEXT") (pin "2") (pinfunction "S1_2") (pintype "passive"))
      (node (ref "R21") (pin "1") (pinfunction "1_1") (pintype "passive"))
    )
    (net (code "35") (name "ETHIS") (class "Default")
      (node (ref "E2") (pin "12") (pinfunction "I0_12") (pintype "input"))
      (node (ref "E2") (pin "4") (pinfunction "I0_4") (pintype "input"))
      (node (ref "ETHIS") (pin "1") (pinfunction "S_1") (pintype "passive"))
      (node (ref "ETHIS") (pin "2") (pinfunction "S1_2") (pintype "passive"))
      (node (ref "R20") (pin "1") (pinfunction "1_1") (pintype "passive"))
    )
    (net (code "36") (name "GND") (class "Default")
      (node (ref "!SHLT") (pin "3") (pinfunction "P_3") (pintype "passive"))
      (node (ref "!SHLT") (pin "4") (pinfunction "P1_4") (pintype "passive"))
      (node (ref "BOOT") (pin "3") (pinfunction "P_3") (pintype "passive"))
      (node (ref "BOOT") (pin "4") (pinfunction "P1_4") (pintype "passive"))
      (node (ref "C1") (pin "2") (pinfunction "2_2") (pintype "passive"))
      (node (ref "C10") (pin "2") (pinfunction "2_2") (pintype "passive"))
      (node (ref "C11") (pin "2") (pinfunction "2_2") (pintype "passive"))
      (node (ref "C12") (pin "2") (pinfunction "2_2") (pintype "passive"))
      (node (ref "C13") (pin "2") (pinfunction "2_2") (pintype "passive"))
      (node (ref "C14") (pin "2") (pinfunction "2_2") (pintype "passive"))
      (node (ref "C15") (pin "2") (pinfunction "2_2") (pintype "passive"))
      (node (ref "C16") (pin "2") (pinfunction "2_2") (pintype "passive"))
      (node (ref "C19") (pin "-") (pinfunction "-_-") (pintype "passive"))
      (node (ref "C2") (pin "2") (pinfunction "2_2") (pintype "passive"))
      (node (ref "C20") (pin "-") (pinfunction "-_-") (pintype "passive"))
      (node (ref "C3") (pin "2") (pinfunction "2_2") (pintype "passive"))
      (node (ref "C4") (pin "2") (pinfunction "2_2") (pintype "passive"))
      (node (ref "C5") (pin "2") (pinfunction "2_2") (pintype "passive"))
      (node (ref "C6") (pin "2") (pinfunction "2_2") (pintype "passive"))
      (node (ref "C7") (pin "2") (pinfunction "2_2") (pintype "passive"))
      (node (ref "C8") (pin "2") (pinfunction "2_2") (pintype "passive"))
      (node (ref "C9") (pin "2") (pinfunction "2_2") (pintype "passive"))
      (node (ref "DISP") (pin "3") (pinfunction "P_3") (pintype "passive"))
      (node (ref "DISP") (pin "4") (pinfunction "P1_4") (pintype "passive"))
      (node (ref "DNEXT") (pin "3") (pinfunction "P_3") (pintype "passive"))
      (node (ref "DNEXT") (pin "4") (pinfunction "P1_4") (pintype "passive"))
      (node (ref "DTHIS") (pin "3") (pinfunction "P_3") (pintype "passive"))
      (node (ref "DTHIS") (pin "4") (pinfunction "P1_4") (pintype "passive"))
      (node (ref "E1") (pin "5") (pinfunction "EI_5") (pintype "input"))
      (node (ref "E13") (pin "6") (pinfunction "ID_6") (pintype "input"))
      (node (ref "E16") (pin "6") (pinfunction "ID_6") (pintype "input"))
      (node (ref "E18") (pin "9") (pinfunction "A_9") (pintype "input"))
      (node (ref "E22") (pin "12") (pinfunction "D_12") (pintype "input"))
      (node (ref "E24") (pin "6") (pinfunction "MOD_6") (pintype "input"))
      (node (ref "E25") (pin "2") (pinfunction "R0(1)_2") (pintype "input"))
      (node (ref "E25") (pin "3") (pinfunction "R0(2)_3") (pintype "input"))
      (node (ref "E25") (pin "6") (pinfunction "R9(1)_6") (pintype "input"))
      (node (ref "E25") (pin "7") (pinfunction "R9(2)_7") (pintype "input"))
      (node (ref "E8") (pin "6") (pinfunction "ID_6") (pintype "input"))
      (node (ref "ENEXT") (pin "3") (pinfunction "P_3") (pintype "passive"))
      (node (ref "ENEXT") (pin "4") (pinfunction "P1_4") (pintype "passive"))
      (node (ref "ETHIS") (pin "3") (pinfunction "P_3") (pintype "passive"))
      (node (ref "ETHIS") (pin "4") (pinfunction "P1_4") (pintype "passive"))
      (node (ref "GND") (pin "1") (pinfunction "P_1") (pintype "passive"))
      (node (ref "INIT") (pin "3") (pinfunction "P_3") (pintype "passive"))
      (node (ref "INIT") (pin "4") (pinfunction "P1_4") (pintype "passive"))
      (node (ref "J1") (pin "8") (pinfunction "8_8") (pintype "passive"))
      (node (ref "J2") (pin "8") (pinfunction "8_8") (pintype "passive"))
      (node (ref "KEY0") (pin "3") (pinfunction "P_3") (pintype "passive"))
      (node (ref "KEY0") (pin "4") (pinfunction "P1_4") (pintype "passive"))
      (node (ref "KEY1") (pin "3") (pinfunction "P_3") (pintype "passive"))
      (node (ref "KEY1") (pin "4") (pinfunction "P1_4") (pintype "passive"))
      (node (ref "KEY2") (pin "3") (pinfunction "P_3") (pintype "passive"))
      (node (ref "KEY2") (pin "4") (pinfunction "P1_4") (pintype "passive"))
      (node (ref "KEY3") (pin "3") (pinfunction "P_3") (pintype "passive"))
      (node (ref "KEY3") (pin "4") (pinfunction "P1_4") (pintype "passive"))
      (node (ref "KEY4") (pin "3") (pinfunction "P_3") (pintype "passive"))
      (node (ref "KEY4") (pin "4") (pinfunction "P1_4") (pintype "passive"))
      (node (ref "KEY5") (pin "3") (pinfunction "P_3") (pintype "passive"))
      (node (ref "KEY5") (pin "4") (pinfunction "P1_4") (pintype "passive"))
      (node (ref "KEY6") (pin "3") (pinfunction "P_3") (pintype "passive"))
      (node (ref "KEY6") (pin "4") (pinfunction "P1_4") (pintype "passive"))
      (node (ref "KEY7") (pin "3") (pinfunction "P_3") (pintype "passive"))
      (node (ref "KEY7") (pin "4") (pinfunction "P1_4") (pintype "passive"))
      (node (ref "LA") (pin "3") (pinfunction "P_3") (pintype "passive"))
      (node (ref "LA") (pin "4") (pinfunction "P1_4") (pintype "passive"))
      (node (ref "LSR") (pin "3") (pinfunction "P_3") (pintype "passive"))
      (node (ref "LSR") (pin "4") (pinfunction "P1_4") (pintype "passive"))
      (node (ref "LXA") (pin "3") (pinfunction "P_3") (pintype "passive"))
      (node (ref "LXA") (pin "4") (pinfunction "P1_4") (pintype "passive"))
      (node (ref "RUN") (pin "3") (pinfunction "P_3") (pintype "passive"))
      (node (ref "RUN") (pin "4") (pinfunction "P1_4") (pintype "passive"))
    )
    (net (code "37") (name "INIT") (class "Default")
      (node (ref "E6") (pin "13") (pinfunction "3_13") (pintype "input"))
      (node (ref "INIT") (pin "1") (pinfunction "S_1") (pintype "passive"))
      (node (ref "INIT") (pin "2") (pinfunction "S1_2") (pintype "passive"))
      (node (ref "R8") (pin "1") (pinfunction "1_1") (pintype "passive"))
    )
    (net (code "38") (name "KEY0") (class "Default")
      (node (ref "E1") (pin "4") (pinfunction "7_4") (pintype "input"))
      (node (ref "KEY0") (pin "1") (pinfunction "S_1") (pintype "passive"))
      (node (ref "KEY0") (pin "2") (pinfunction "S1_2") (pintype "passive"))
      (node (ref "R18") (pin "1") (pinfunction "1_1") (pintype "passive"))
    )
    (net (code "39") (name "KEY1") (class "Default")
      (node (ref "E1") (pin "3") (pinfunction "6_3") (pintype "input"))
      (node (ref "KEY1") (pin "1") (pinfunction "S_1") (pintype "passive"))
      (node (ref "KEY1") (pin "2") (pinfunction "S1_2") (pintype "passive"))
      (node (ref "R17") (pin "1") (pinfunction "1_1") (pintype "passive"))
    )
    (net (code "40") (name "KEY2") (class "Default")
      (node (ref "E1") (pin "2") (pinfunction "5_2") (pintype "input"))
      (node (ref "KEY2") (pin "1") (pinfunction "S_1") (pintype "passive"))
      (node (ref "KEY2") (pin "2") (pinfunction "S1_2") (pintype "passive"))
      (node (ref "R16") (pin "1") (pinfunction "1_1") (pintype "passive"))
    )
    (net (code "41") (name "KEY3") (class "Default")
      (node (ref "E1") (pin "1") (pinfunction "4_1") (pintype "input"))
      (node (ref "KEY3") (pin "1") (pinfunction "S_1") (pintype "passive"))
      (node (ref "KEY3") (pin "2") (pinfunction "S1_2") (pintype "passive"))
      (node (ref "R15") (pin "1") (pinfunction "1_1") (pintype "passive"))
    )
    (net (code "42") (name "KEY4") (class "Default")
      (node (ref "E1") (pin "13") (pinfunction "3_13") (pintype "input"))
      (node (ref "KEY4") (pin "1") (pinfunction "S_1") (pintype "passive"))
      (node (ref "KEY4") (pin "2") (pinfunction "S1_2") (pintype "passive"))
      (node (ref "R14") (pin "1") (pinfunction "1_1") (pintype "passive"))
    )
    (net (code "43") (name "KEY5") (class "Default")
      (node (ref "E1") (pin "12") (pinfunction "2_12") (pintype "input"))
      (node (ref "KEY5") (pin "1") (pinfunction "S_1") (pintype "passive"))
      (node (ref "KEY5") (pin "2") (pinfunction "S1_2") (pintype "passive"))
      (node (ref "R13") (pin "1") (pinfunction "1_1") (pintype "passive"))
    )
    (net (code "44") (name "KEY6") (class "Default")
      (node (ref "E1") (pin "11") (pinfunction "1_11") (pintype "input"))
      (node (ref "KEY6") (pin "1") (pinfunction "S_1") (pintype "passive"))
      (node (ref "KEY6") (pin "2") (pinfunction "S1_2") (pintype "passive"))
      (node (ref "R12") (pin "1") (pinfunction "1_1") (pintype "passive"))
    )
    (net (code "45") (name "KEY7") (class "Default")
      (node (ref "E1") (pin "10") (pinfunction "0_10") (pintype "input"))
      (node (ref "KEY7") (pin "1") (pinfunction "S_1") (pintype "passive"))
      (node (ref "KEY7") (pin "2") (pinfunction "S1_2") (pintype "passive"))
      (node (ref "R11") (pin "1") (pinfunction "1_1") (pintype "passive"))
    )
    (net (code "46") (name "KEYSTB") (class "Default")
      (node (ref "E23") (pin "9") (pinfunction "Q_9") (pintype "output"))
      (node (ref "J2") (pin "2") (pinfunction "2_2") (pintype "passive"))
    )
    (net (code "47") (name "LA") (class "Default")
      (node (ref "E6") (pin "2") (pinfunction "5_2") (pintype "input"))
      (node (ref "LA") (pin "1") (pinfunction "S_1") (pintype "passive"))
      (node (ref "LA") (pin "2") (pinfunction "S1_2") (pintype "passive"))
      (node (ref "R6") (pin "1") (pinfunction "1_1") (pintype "passive"))
    )
    (net (code "48") (name "LSR") (class "Default")
      (node (ref "E6") (pin "3") (pinfunction "6_3") (pintype "input"))
      (node (ref "LSR") (pin "1") (pinfunction "S_1") (pintype "passive"))
      (node (ref "LSR") (pin "2") (pinfunction "S1_2") (pintype "passive"))
      (node (ref "R5") (pin "1") (pinfunction "1_1") (pintype "passive"))
    )
    (net (code "49") (name "LXA") (class "Default")
      (node (ref "E6") (pin "1") (pinfunction "4_1") (pintype "input"))
      (node (ref "LXA") (pin "1") (pinfunction "S_1") (pintype "passive"))
      (node (ref "LXA") (pin "2") (pinfunction "S1_2") (pintype "passive"))
      (node (ref "R7") (pin "1") (pinfunction "1_1") (pintype "passive"))
    )
    (net (code "50") (name "MCLOCK") (class "Default")
      (node (ref "E20") (pin "4") (pinfunction "O_4") (pintype "output"))
      (node (ref "E23") (pin "13") (pinfunction "CLR_13") (pintype "input"))
      (node (ref "E25") (pin "14") (pinfunction "CKA_14") (pintype "input"))
    )
    (net (code "51") (name "MPXA") (class "Default")
      (node (ref "E22") (pin "14") (pinfunction "B_14") (pintype "input"))
      (node (ref "E25") (pin "8") (pinfunction "QC_8") (pintype "output"))
      (node (ref "J2") (pin "14") (pinfunction "14_14") (pintype "passive"))
    )
    (net (code "52") (name "MPXB") (class "Default")
      (node (ref "E22") (pin "15") (pinfunction "A_15") (pintype "input"))
      (node (ref "E25") (pin "9") (pinfunction "QB_9") (pintype "output"))
      (node (ref "J2") (pin "13") (pinfunction "13_13") (pintype "passive"))
    )
    (net (code "53") (name "NUM") (class "Default")
      (node (ref "E20") (pin "10") (pinfunction "O_10") (pintype "output"))
      (node (ref "J2") (pin "11") (pinfunction "11_11") (pintype "passive"))
    )
    (net (code "54") (name "Net-(D1-C)") (class "Default")
      (node (ref "D1") (pin "K") (pinfunction "C_K") (pintype "passive"))
      (node (ref "E17") (pin "2") (pinfunction "1_2") (pintype "output"))
    )
    (net (code "55") (name "Net-(D1-PadA)") (class "Default")
      (node (ref "D1") (pin "A") (pinfunction "A_A") (pintype "passive"))
      (node (ref "R44") (pin "1") (pinfunction "1_1") (pintype "passive"))
    )
    (net (code "56") (name "Net-(D2-C)") (class "Default")
      (node (ref "D2") (pin "K") (pinfunction "C_K") (pintype "passive"))
      (node (ref "E17") (pin "5") (pinfunction "4_5") (pintype "output"))
    )
    (net (code "57") (name "Net-(D2-PadA)") (class "Default")
      (node (ref "D2") (pin "A") (pinfunction "A_A") (pintype "passive"))
      (node (ref "R41") (pin "1") (pinfunction "1_1") (pintype "passive"))
    )
    (net (code "58") (name "Net-(D3-C)") (class "Default")
      (node (ref "D3") (pin "K") (pinfunction "C_K") (pintype "passive"))
      (node (ref "E17") (pin "7") (pinfunction "6_7") (pintype "output"))
    )
    (net (code "59") (name "Net-(D3-PadA)") (class "Default")
      (node (ref "D3") (pin "A") (pinfunction "A_A") (pintype "passive"))
      (node (ref "R39") (pin "1") (pinfunction "1_1") (pintype "passive"))
    )
    (net (code "60") (name "Net-(D4-C)") (class "Default")
      (node (ref "D4") (pin "K") (pinfunction "C_K") (pintype "passive"))
      (node (ref "E17") (pin "1") (pinfunction "0_1") (pintype "output"))
    )
    (net (code "61") (name "Net-(D4-PadA)") (class "Default")
      (node (ref "D4") (pin "A") (pinfunction "A_A") (pintype "passive"))
      (node (ref "R45") (pin "1") (pinfunction "1_1") (pintype "passive"))
    )
    (net (code "62") (name "Net-(D5-C)") (class "Default")
      (node (ref "D5") (pin "K") (pinfunction "C_K") (pintype "passive"))
      (node (ref "E17") (pin "4") (pinfunction "3_4") (pintype "output"))
    )
    (net (code "63") (name "Net-(D5-PadA)") (class "Default")
      (node (ref "D5") (pin "A") (pinfunction "A_A") (pintype "passive"))
      (node (ref "R42") (pin "1") (pinfunction "1_1") (pintype "passive"))
    )
    (net (code "64") (name "Net-(D6-C)") (class "Default")
      (node (ref "D6") (pin "K") (pinfunction "C_K") (pintype "passive"))
      (node (ref "E17") (pin "6") (pinfunction "5_6") (pintype "output"))
    )
    (net (code "65") (name "Net-(D6-PadA)") (class "Default")
      (node (ref "D6") (pin "A") (pinfunction "A_A") (pintype "passive"))
      (node (ref "R40") (pin "1") (pinfunction "1_1") (pintype "passive"))
    )
    (net (code "66") (name "Net-(D7-C)") (class "Default")
      (node (ref "D7") (pin "K") (pinfunction "C_K") (pintype "passive"))
      (node (ref "E17") (pin "3") (pinfunction "2_3") (pintype "output"))
    )
    (net (code "67") (name "Net-(D7-PadA)") (class "Default")
      (node (ref "D7") (pin "A") (pinfunction "A_A") (pintype "passive"))
      (node (ref "R43") (pin "1") (pinfunction "1_1") (pintype "passive"))
    )
    (net (code "68") (name "Net-(D8-C)") (class "Default")
      (node (ref "D8") (pin "K") (pinfunction "C_K") (pintype "passive"))
      (node (ref "E19") (pin "2") (pinfunction "O_2") (pintype "open_collector"))
    )
    (net (code "69") (name "Net-(D8-PadA)") (class "Default")
      (node (ref "D8") (pin "A") (pinfunction "A_A") (pintype "passive"))
      (node (ref "R46") (pin "1") (pinfunction "1_1") (pintype "passive"))
    )
    (net (code "70") (name "Net-(E1A-EO)") (class "Default")
      (node (ref "E1") (pin "15") (pinfunction "EO_15") (pintype "output"))
      (node (ref "E6") (pin "5") (pinfunction "EI_5") (pintype "input"))
    )
    (net (code "71") (name "Net-(E1A-GS)") (class "Default")
      (node (ref "E1") (pin "14") (pinfunction "GS_14") (pintype "output"))
      (node (ref "E20") (pin "11") (pinfunction "I_11") (pintype "input"))
      (node (ref "E21") (pin "9") (pinfunction "I0_9") (pintype "input"))
    )
    (net (code "72") (name "Net-(E2A-O)") (class "Default")
      (node (ref "E2") (pin "3") (pinfunction "O_3") (pintype "output"))
      (node (ref "E6") (pin "12") (pinfunction "2_12") (pintype "input"))
    )
    (net (code "73") (name "Net-(E2C-O)") (class "Default")
      (node (ref "E2") (pin "8") (pinfunction "O_8") (pintype "output"))
      (node (ref "E6") (pin "10") (pinfunction "0_10") (pintype "input"))
    )
    (net (code "74") (name "Net-(E2D-O)") (class "Default")
      (node (ref "E2") (pin "11") (pinfunction "O_11") (pintype "output"))
      (node (ref "E6") (pin "11") (pinfunction "1_11") (pintype "input"))
    )
    (net (code "75") (name "Net-(E10A-I0)") (class "Default")
      (node (ref "E10") (pin "1") (pinfunction "I0_1") (pintype "input"))
      (node (ref "E18") (pin "12") (pinfunction "~{Q}_12") (pintype "output"))
    )
    (net (code "76") (name "Net-(E10B-I0)") (class "Default")
      (node (ref "E1") (pin "9") (pinfunction "A0_9") (pintype "output"))
      (node (ref "E10") (pin "4") (pinfunction "I0_4") (pintype "input"))
    )
    (net (code "77") (name "Net-(E10B-I1)") (class "Default")
      (node (ref "E10") (pin "5") (pinfunction "I1_5") (pintype "input"))
      (node (ref "E6") (pin "9") (pinfunction "A0_9") (pintype "output"))
    )
    (net (code "78") (name "Net-(E10C-I0)") (class "Default")
      (node (ref "E10") (pin "9") (pinfunction "I0_9") (pintype "input"))
      (node (ref "E6") (pin "7") (pinfunction "A1_7") (pintype "output"))
    )
    (net (code "79") (name "Net-(E10C-I1)") (class "Default")
      (node (ref "E1") (pin "7") (pinfunction "A1_7") (pintype "output"))
      (node (ref "E10") (pin "10") (pinfunction "I1_10") (pintype "input"))
    )
    (net (code "80") (name "Net-(E10D-I0)") (class "Default")
      (node (ref "E10") (pin "12") (pinfunction "I0_12") (pintype "input"))
      (node (ref "E6") (pin "6") (pinfunction "A2_6") (pintype "output"))
    )
    (net (code "81") (name "Net-(E10D-I1)") (class "Default")
      (node (ref "E1") (pin "6") (pinfunction "A2_6") (pintype "output"))
      (node (ref "E10") (pin "13") (pinfunction "I1_13") (pintype "input"))
    )
    (net (code "82") (name "Net-(E15-A)") (class "Default")
      (node (ref "E15") (pin "7") (pinfunction "A_7") (pintype "passive"))
      (node (ref "E16") (pin "13") (pinfunction "A_13") (pintype "open_collector"))
    )
    (net (code "83") (name "Net-(E15-B)") (class "Default")
      (node (ref "E15") (pin "6") (pinfunction "B_6") (pintype "passive"))
      (node (ref "E16") (pin "12") (pinfunction "B_12") (pintype "open_collector"))
    )
    (net (code "84") (name "Net-(E15-C)") (class "Default")
      (node (ref "E15") (pin "4") (pinfunction "C_4") (pintype "passive"))
      (node (ref "E16") (pin "11") (pinfunction "C_11") (pintype "open_collector"))
    )
    (net (code "85") (name "Net-(E15-D)") (class "Default")
      (node (ref "E15") (pin "2") (pinfunction "D_2") (pintype "passive"))
      (node (ref "E16") (pin "10") (pinfunction "D_10") (pintype "open_collector"))
    )
    (net (code "86") (name "Net-(E15-E)") (class "Default")
      (node (ref "E15") (pin "1") (pinfunction "E_1") (pintype "passive"))
      (node (ref "E16") (pin "9") (pinfunction "E_9") (pintype "open_collector"))
    )
    (net (code "87") (name "Net-(E15-F)") (class "Default")
      (node (ref "E15") (pin "9") (pinfunction "F_9") (pintype "passive"))
      (node (ref "E16") (pin "15") (pinfunction "F_15") (pintype "open_collector"))
    )
    (net (code "88") (name "Net-(E15-G)") (class "Default")
      (node (ref "E15") (pin "10") (pinfunction "G_10") (pintype "passive"))
      (node (ref "E16") (pin "14") (pinfunction "G_14") (pintype "open_collector"))
    )
    (net (code "89") (name "Net-(E18A-A)") (class "Default")
      (node (ref "E18") (pin "1") (pinfunction "A_1") (pintype "input"))
      (node (ref "E18") (pin "5") (pinfunction "Q_5") (pintype "output"))
    )
    (net (code "90") (name "Net-(E18A-C)") (class "Default")
      (node (ref "C17") (pin "-") (pinfunction "-_-") (pintype "passive"))
      (node (ref "E18") (pin "14") (pinfunction "C_14") (pintype "input"))
    )
    (net (code "91") (name "Net-(E18A-R{slash}C)") (class "Default")
      (node (ref "C17") (pin "+") (pinfunction "+_+") (pintype "passive"))
      (node (ref "E18") (pin "15") (pinfunction "R/C_15") (pintype "input"))
      (node (ref "R2") (pin "2") (pinfunction "2_2") (pintype "passive"))
    )
    (net (code "92") (name "Net-(E18A-~{Q})") (class "Default")
      (node (ref "E18") (pin "10") (pinfunction "B_10") (pintype "input"))
      (node (ref "E18") (pin "4") (pinfunction "~{Q}_4") (pintype "output"))
    )
    (net (code "93") (name "Net-(E18B-C)") (class "Default")
      (node (ref "C18") (pin "2") (pinfunction "2_2") (pintype "passive"))
      (node (ref "C21") (pin "2") (pinfunction "2_2") (pintype "passive"))
      (node (ref "E18") (pin "6") (pinfunction "C_6") (pintype "input"))
    )
    (net (code "94") (name "Net-(E18B-R{slash}C)") (class "Default")
      (node (ref "C18") (pin "1") (pinfunction "1_1") (pintype "passive"))
      (node (ref "C21") (pin "1") (pinfunction "1_1") (pintype "passive"))
      (node (ref "E18") (pin "7") (pinfunction "R/C_7") (pintype "input"))
      (node (ref "R1") (pin "1") (pinfunction "1_1") (pintype "passive"))
    )
    (net (code "95") (name "Net-(E19B-I)") (class "Default")
      (node (ref "E19") (pin "3") (pinfunction "I_3") (pintype "input"))
      (node (ref "E22") (pin "4") (pinfunction "O3_4") (pintype "output"))
    )
    (net (code "96") (name "Net-(E19B-O)") (class "Default")
      (node (ref "E19") (pin "4") (pinfunction "O_4") (pintype "open_collector"))
      (node (ref "R27") (pin "1") (pinfunction "1_1") (pintype "passive"))
      (node (ref "R34") (pin "1") (pinfunction "1_1") (pintype "passive"))
    )
    (net (code "97") (name "Net-(E19C-I)") (class "Default")
      (node (ref "E19") (pin "5") (pinfunction "I_5") (pintype "input"))
      (node (ref "E22") (pin "5") (pinfunction "O4_5") (pintype "output"))
    )
    (net (code "98") (name "Net-(E19C-O)") (class "Default")
      (node (ref "E19") (pin "6") (pinfunction "O_6") (pintype "open_collector"))
      (node (ref "R28") (pin "1") (pinfunction "1_1") (pintype "passive"))
      (node (ref "R38") (pin "1") (pinfunction "1_1") (pintype "passive"))
    )
    (net (code "99") (name "Net-(E19D-I)") (class "Default")
      (node (ref "E19") (pin "9") (pinfunction "I_9") (pintype "input"))
      (node (ref "E22") (pin "3") (pinfunction "O2_3") (pintype "output"))
    )
    (net (code "100") (name "Net-(E19D-O)") (class "Default")
      (node (ref "E19") (pin "8") (pinfunction "O_8") (pintype "open_collector"))
      (node (ref "R26") (pin "1") (pinfunction "1_1") (pintype "passive"))
      (node (ref "R35") (pin "1") (pinfunction "1_1") (pintype "passive"))
    )
    (net (code "101") (name "Net-(E19E-I)") (class "Default")
      (node (ref "E19") (pin "11") (pinfunction "I_11") (pintype "input"))
      (node (ref "E22") (pin "2") (pinfunction "O1_2") (pintype "output"))
    )
    (net (code "102") (name "Net-(E19E-O)") (class "Default")
      (node (ref "E19") (pin "10") (pinfunction "O_10") (pintype "open_collector"))
      (node (ref "R25") (pin "1") (pinfunction "1_1") (pintype "passive"))
      (node (ref "R36") (pin "1") (pinfunction "1_1") (pintype "passive"))
    )
    (net (code "103") (name "Net-(E19F-I)") (class "Default")
      (node (ref "E19") (pin "13") (pinfunction "I_13") (pintype "input"))
      (node (ref "E22") (pin "1") (pinfunction "O0_1") (pintype "output"))
    )
    (net (code "104") (name "Net-(E19F-O)") (class "Default")
      (node (ref "E19") (pin "12") (pinfunction "O_12") (pintype "open_collector"))
      (node (ref "R24") (pin "1") (pinfunction "1_1") (pintype "passive"))
      (node (ref "R37") (pin "1") (pinfunction "1_1") (pintype "passive"))
    )
    (net (code "105") (name "Net-(E20A-I)") (class "Default")
      (node (ref "E20") (pin "1") (pinfunction "I_1") (pintype "input"))
      (node (ref "E21") (pin "5") (pinfunction "I3_5") (pintype "input"))
      (node (ref "E24") (pin "10") (pinfunction "QD_10") (pintype "output"))
    )
    (net (code "106") (name "Net-(E20A-O)") (class "Default")
      (node (ref "E20") (pin "2") (pinfunction "O_2") (pintype "output"))
      (node (ref "E23") (pin "3") (pinfunction "CLK_3") (pintype "input"))
    )
    (net (code "107") (name "Net-(E20F-I)") (class "Default")
      (node (ref "E20") (pin "13") (pinfunction "I_13") (pintype "input"))
      (node (ref "E21") (pin "8") (pinfunction "O_8") (pintype "output"))
      (node (ref "E23") (pin "2") (pinfunction "D_2") (pintype "input"))
    )
    (net (code "108") (name "Net-(E20F-O)") (class "Default")
      (node (ref "E20") (pin "12") (pinfunction "O_12") (pintype "output"))
      (node (ref "E24") (pin "1") (pinfunction "SER_1") (pintype "input"))
    )
    (net (code "109") (name "Net-(E21A-I0)") (class "Default")
      (node (ref "E21") (pin "1") (pinfunction "I0_1") (pintype "input"))
      (node (ref "E24") (pin "13") (pinfunction "QA_13") (pintype "output"))
    )
    (net (code "110") (name "Net-(E21A-I1)") (class "Default")
      (node (ref "E21") (pin "2") (pinfunction "I1_2") (pintype "input"))
      (node (ref "E24") (pin "12") (pinfunction "QB_12") (pintype "output"))
    )
    (net (code "111") (name "Net-(E21A-I2)") (class "Default")
      (node (ref "E21") (pin "4") (pinfunction "I2_4") (pintype "input"))
      (node (ref "E24") (pin "11") (pinfunction "QC_11") (pintype "output"))
    )
    (net (code "112") (name "Net-(E21A-O)") (class "Default")
      (node (ref "E21") (pin "6") (pinfunction "O_6") (pintype "output"))
      (node (ref "E23") (pin "1") (pinfunction "CLR_1") (pintype "input"))
    )
    (net (code "113") (name "Net-(E22A-C)") (class "Default")
      (node (ref "E22") (pin "13") (pinfunction "C_13") (pintype "input"))
      (node (ref "E25") (pin "11") (pinfunction "QD_11") (pintype "output"))
    )
    (net (code "114") (name "Net-(E23A-Q)") (class "Default")
      (node (ref "E23") (pin "11") (pinfunction "CLK_11") (pintype "input"))
      (node (ref "E23") (pin "5") (pinfunction "Q_5") (pintype "output"))
    )
    (net (code "115") (name "Net-(E25A-CKB)") (class "Default")
      (node (ref "E25") (pin "1") (pinfunction "CKB_1") (pintype "input"))
      (node (ref "E25") (pin "12") (pinfunction "QA_12") (pintype "output"))
    )
    (net (code "116") (name "Net-(Q1-B)") (class "Default")
      (node (ref "Q1") (pin "2") (pinfunction "B_2") (pintype "passive"))
      (node (ref "R38") (pin "2") (pinfunction "2_2") (pintype "passive"))
    )
    (net (code "117") (name "Net-(Q1-C)") (class "Default")
      (node (ref "Q1") (pin "3") (pinfunction "C_3") (pintype "passive"))
      (node (ref "R33") (pin "1") (pinfunction "1_1") (pintype "passive"))
    )
    (net (code "118") (name "Net-(Q1-E)") (class "Default")
      (node (ref "E15") (pin "3") (pinfunction "CA_3") (pintype "passive"))
      (node (ref "E15") (pin "8") (pinfunction "CA_8") (pintype "passive"))
      (node (ref "Q1") (pin "1") (pinfunction "E_1") (pintype "passive"))
    )
    (net (code "119") (name "Net-(Q2-B)") (class "Default")
      (node (ref "Q2") (pin "2") (pinfunction "B_2") (pintype "passive"))
      (node (ref "R37") (pin "2") (pinfunction "2_2") (pintype "passive"))
    )
    (net (code "120") (name "Net-(Q2-C)") (class "Default")
      (node (ref "Q2") (pin "3") (pinfunction "C_3") (pintype "passive"))
      (node (ref "R29") (pin "2") (pinfunction "2_2") (pintype "passive"))
    )
    (net (code "121") (name "Net-(Q2-E)") (class "Default")
      (node (ref "E3") (pin "3") (pinfunction "CA_3") (pintype "passive"))
      (node (ref "E3") (pin "8") (pinfunction "CA_8") (pintype "passive"))
      (node (ref "E9") (pin "3") (pinfunction "CA_3") (pintype "passive"))
      (node (ref "E9") (pin "8") (pinfunction "CA_8") (pintype "passive"))
      (node (ref "Q2") (pin "1") (pinfunction "E_1") (pintype "passive"))
    )
    (net (code "122") (name "Net-(Q3-B)") (class "Default")
      (node (ref "Q3") (pin "2") (pinfunction "B_2") (pintype "passive"))
      (node (ref "R36") (pin "2") (pinfunction "2_2") (pintype "passive"))
    )
    (net (code "123") (name "Net-(Q3-C)") (class "Default")
      (node (ref "Q3") (pin "3") (pinfunction "C_3") (pintype "passive"))
      (node (ref "R30") (pin "2") (pinfunction "2_2") (pintype "passive"))
    )
    (net (code "124") (name "Net-(Q3-E)") (class "Default")
      (node (ref "E11") (pin "3") (pinfunction "CA_3") (pintype "passive"))
      (node (ref "E11") (pin "8") (pinfunction "CA_8") (pintype "passive"))
      (node (ref "E4") (pin "3") (pinfunction "CA_3") (pintype "passive"))
      (node (ref "E4") (pin "8") (pinfunction "CA_8") (pintype "passive"))
      (node (ref "Q3") (pin "1") (pinfunction "E_1") (pintype "passive"))
    )
    (net (code "125") (name "Net-(Q4-B)") (class "Default")
      (node (ref "Q4") (pin "2") (pinfunction "B_2") (pintype "passive"))
      (node (ref "R35") (pin "2") (pinfunction "2_2") (pintype "passive"))
    )
    (net (code "126") (name "Net-(Q4-C)") (class "Default")
      (node (ref "Q4") (pin "3") (pinfunction "C_3") (pintype "passive"))
      (node (ref "R31") (pin "2") (pinfunction "2_2") (pintype "passive"))
    )
    (net (code "127") (name "Net-(Q4-E)") (class "Default")
      (node (ref "E12") (pin "3") (pinfunction "CA_3") (pintype "passive"))
      (node (ref "E12") (pin "8") (pinfunction "CA_8") (pintype "passive"))
      (node (ref "E5") (pin "3") (pinfunction "CA_3") (pintype "passive"))
      (node (ref "E5") (pin "8") (pinfunction "CA_8") (pintype "passive"))
      (node (ref "Q4") (pin "1") (pinfunction "E_1") (pintype "passive"))
    )
    (net (code "128") (name "Net-(Q5-B)") (class "Default")
      (node (ref "Q5") (pin "2") (pinfunction "B_2") (pintype "passive"))
      (node (ref "R34") (pin "2") (pinfunction "2_2") (pintype "passive"))
    )
    (net (code "129") (name "Net-(Q5-C)") (class "Default")
      (node (ref "Q5") (pin "3") (pinfunction "C_3") (pintype "passive"))
      (node (ref "R32") (pin "2") (pinfunction "2_2") (pintype "passive"))
    )
    (net (code "130") (name "Net-(Q5-E)") (class "Default")
      (node (ref "E14") (pin "3") (pinfunction "CA_3") (pintype "passive"))
      (node (ref "E14") (pin "8") (pinfunction "CA_8") (pintype "passive"))
      (node (ref "E7") (pin "3") (pinfunction "CA_3") (pintype "passive"))
      (node (ref "E7") (pin "8") (pinfunction "CA_8") (pintype "passive"))
      (node (ref "Q5") (pin "1") (pinfunction "E_1") (pintype "passive"))
    )
    (net (code "131") (name "RUN") (class "Default")
      (node (ref "E2") (pin "2") (pinfunction "I1_2") (pintype "input"))
      (node (ref "R9") (pin "1") (pinfunction "1_1") (pintype "passive"))
      (node (ref "RUN") (pin "1") (pinfunction "S_1") (pintype "passive"))
      (node (ref "RUN") (pin "2") (pinfunction "S1_2") (pintype "passive"))
    )
    (net (code "132") (name "VCC") (class "Default")
      (node (ref "C1") (pin "1") (pinfunction "1_1") (pintype "passive"))
      (node (ref "C10") (pin "1") (pinfunction "1_1") (pintype "passive"))
      (node (ref "C11") (pin "1") (pinfunction "1_1") (pintype "passive"))
      (node (ref "C12") (pin "1") (pinfunction "1_1") (pintype "passive"))
      (node (ref "C13") (pin "1") (pinfunction "1_1") (pintype "passive"))
      (node (ref "C14") (pin "1") (pinfunction "1_1") (pintype "passive"))
      (node (ref "C15") (pin "1") (pinfunction "1_1") (pintype "passive"))
      (node (ref "C16") (pin "1") (pinfunction "1_1") (pintype "passive"))
      (node (ref "C19") (pin "+") (pinfunction "+_+") (pintype "passive"))
      (node (ref "C2") (pin "1") (pinfunction "1_1") (pintype "passive"))
      (node (ref "C20") (pin "+") (pinfunction "+_+") (pintype "passive"))
      (node (ref "C3") (pin "1") (pinfunction "1_1") (pintype "passive"))
      (node (ref "C4") (pin "1") (pinfunction "1_1") (pintype "passive"))
      (node (ref "C5") (pin "1") (pinfunction "1_1") (pintype "passive"))
      (node (ref "C6") (pin "1") (pinfunction "1_1") (pintype "passive"))
      (node (ref "C7") (pin "1") (pinfunction "1_1") (pintype "passive"))
      (node (ref "C8") (pin "1") (pinfunction "1_1") (pintype "passive"))
      (node (ref "C9") (pin "1") (pinfunction "1_1") (pintype "passive"))
      (node (ref "E13") (pin "3") (pinfunction "LT_3") (pintype "input"))
      (node (ref "E13") (pin "4") (pinfunction "BI/RBO_4") (pintype "input"))
      (node (ref "E13") (pin "5") (pinfunction "RBI_5") (pintype "input"))
      (node (ref "E16") (pin "3") (pinfunction "LT_3") (pintype "input"))
      (node (ref "E16") (pin "4") (pinfunction "BI/RBO_4") (pintype "input"))
      (node (ref "E16") (pin "5") (pinfunction "RBI_5") (pintype "input"))
      (node (ref "E18") (pin "3") (pinfunction "CLR_3") (pintype "input"))
      (node (ref "E23") (pin "10") (pinfunction "PRE_10") (pintype "input"))
      (node (ref "E23") (pin "12") (pinfunction "D_12") (pintype "input"))
      (node (ref "E23") (pin "4") (pinfunction "PRE_4") (pintype "input"))
      (node (ref "E24") (pin "2") (pinfunction "A_2") (pintype "input"))
      (node (ref "E24") (pin "3") (pinfunction "B_3") (pintype "input"))
      (node (ref "E24") (pin "4") (pinfunction "C_4") (pintype "input"))
      (node (ref "E24") (pin "5") (pinfunction "D_5") (pintype "input"))
      (node (ref "E24") (pin "8") (pinfunction "CK2_8") (pintype "input"))
      (node (ref "E8") (pin "3") (pinfunction "LT_3") (pintype "input"))
      (node (ref "E8") (pin "4") (pinfunction "BI/RBO_4") (pintype "input"))
      (node (ref "E8") (pin "5") (pinfunction "RBI_5") (pintype "input"))
      (node (ref "J1") (pin "16") (pinfunction "16_16") (pintype "passive"))
      (node (ref "J2") (pin "16") (pinfunction "16_16") (pintype "passive"))
      (node (ref "R1") (pin "2") (pinfunction "2_2") (pintype "passive"))
      (node (ref "R10") (pin "2") (pinfunction "2_2") (pintype "passive"))
      (node (ref "R11") (pin "2") (pinfunction "2_2") (pintype "passive"))
      (node (ref "R12") (pin "2") (pinfunction "2_2") (pintype "passive"))
      (node (ref "R13") (pin "2") (pinfunction "2_2") (pintype "passive"))
      (node (ref "R14") (pin "2") (pinfunction "2_2") (pintype "passive"))
      (node (ref "R15") (pin "2") (pinfunction "2_2") (pintype "passive"))
      (node (ref "R16") (pin "2") (pinfunction "2_2") (pintype "passive"))
      (node (ref "R17") (pin "2") (pinfunction "2_2") (pintype "passive"))
      (node (ref "R18") (pin "2") (pinfunction "2_2") (pintype "passive"))
      (node (ref "R19") (pin "2") (pinfunction "2_2") (pintype "passive"))
      (node (ref "R2") (pin "1") (pinfunction "1_1") (pintype "passive"))
      (node (ref "R20") (pin "2") (pinfunction "2_2") (pintype "passive"))
      (node (ref "R21") (pin "2") (pinfunction "2_2") (pintype "passive"))
      (node (ref "R22") (pin "2") (pinfunction "2_2") (pintype "passive"))
      (node (ref "R23") (pin "2") (pinfunction "2_2") (pintype "passive"))
      (node (ref "R24") (pin "2") (pinfunction "2_2") (pintype "passive"))
      (node (ref "R25") (pin "2") (pinfunction "2_2") (pintype "passive"))
      (node (ref "R26") (pin "2") (pinfunction "2_2") (pintype "passive"))
      (node (ref "R27") (pin "2") (pinfunction "2_2") (pintype "passive"))
      (node (ref "R28") (pin "2") (pinfunction "2_2") (pintype "passive"))
      (node (ref "R29") (pin "1") (pinfunction "1_1") (pintype "passive"))
      (node (ref "R3") (pin "2") (pinfunction "2_2") (pintype "passive"))
      (node (ref "R30") (pin "1") (pinfunction "1_1") (pintype "passive"))
      (node (ref "R31") (pin "1") (pinfunction "1_1") (pintype "passive"))
      (node (ref "R32") (pin "1") (pinfunction "1_1") (pintype "passive"))
      (node (ref "R33") (pin "2") (pinfunction "2_2") (pintype "passive"))
      (node (ref "R39") (pin "2") (pinfunction "2_2") (pintype "passive"))
      (node (ref "R4") (pin "1") (pinfunction "1_1") (pintype "passive"))
      (node (ref "R40") (pin "2") (pinfunction "2_2") (pintype "passive"))
      (node (ref "R41") (pin "2") (pinfunction "2_2") (pintype "passive"))
      (node (ref "R42") (pin "2") (pinfunction "2_2") (pintype "passive"))
      (node (ref "R43") (pin "2") (pinfunction "2_2") (pintype "passive"))
      (node (ref "R44") (pin "2") (pinfunction "2_2") (pintype "passive"))
      (node (ref "R45") (pin "2") (pinfunction "2_2") (pintype "passive"))
      (node (ref "R46") (pin "2") (pinfunction "2_2") (pintype "passive"))
      (node (ref "R5") (pin "2") (pinfunction "2_2") (pintype "passive"))
      (node (ref "R6") (pin "2") (pinfunction "2_2") (pintype "passive"))
      (node (ref "R7") (pin "2") (pinfunction "2_2") (pintype "passive"))
      (node (ref "R8") (pin "2") (pinfunction "2_2") (pintype "passive"))
      (node (ref "R9") (pin "2") (pinfunction "2_2") (pintype "passive"))
      (node (ref "VCC") (pin "1") (pinfunction "P_1") (pintype "passive"))
    )
    (net (code "133") (name "unconnected-(E3-DP-Pad5)") (class "Default")
      (node (ref "E3") (pin "5") (pinfunction "DP_5") (pintype "passive"))
    )
    (net (code "134") (name "unconnected-(E4-DP-Pad5)") (class "Default")
      (node (ref "E4") (pin "5") (pinfunction "DP_5") (pintype "passive"))
    )
    (net (code "135") (name "unconnected-(E5-DP-Pad5)") (class "Default")
      (node (ref "E5") (pin "5") (pinfunction "DP_5") (pintype "passive"))
    )
    (net (code "136") (name "unconnected-(E6A-EO-Pad15)") (class "Default")
      (node (ref "E6") (pin "15") (pinfunction "EO_15") (pintype "output"))
    )
    (net (code "137") (name "unconnected-(E7-DP-Pad5)") (class "Default")
      (node (ref "E7") (pin "5") (pinfunction "DP_5") (pintype "passive"))
    )
    (net (code "138") (name "unconnected-(E9-DP-Pad5)") (class "Default")
      (node (ref "E9") (pin "5") (pinfunction "DP_5") (pintype "passive"))
    )
    (net (code "139") (name "unconnected-(E11-DP-Pad5)") (class "Default")
      (node (ref "E11") (pin "5") (pinfunction "DP_5") (pintype "passive"))
    )
    (net (code "140") (name "unconnected-(E12-DP-Pad5)") (class "Default")
      (node (ref "E12") (pin "5") (pinfunction "DP_5") (pintype "passive"))
    )
    (net (code "141") (name "unconnected-(E14-DP-Pad5)") (class "Default")
      (node (ref "E14") (pin "5") (pinfunction "DP_5") (pintype "passive"))
    )
    (net (code "142") (name "unconnected-(E15-DP-Pad5)") (class "Default")
      (node (ref "E15") (pin "5") (pinfunction "DP_5") (pintype "passive"))
    )
    (net (code "143") (name "unconnected-(E17A-7-Pad9)") (class "Default")
      (node (ref "E17") (pin "9") (pinfunction "7_9") (pintype "output"))
    )
    (net (code "144") (name "unconnected-(E17A-8-Pad10)") (class "Default")
      (node (ref "E17") (pin "10") (pinfunction "8_10") (pintype "output"))
    )
    (net (code "145") (name "unconnected-(E17A-9-Pad11)") (class "Default")
      (node (ref "E17") (pin "11") (pinfunction "9_11") (pintype "output"))
    )
    (net (code "146") (name "unconnected-(E18A-Q-Pad13)") (class "Default")
      (node (ref "E18") (pin "13") (pinfunction "Q_13") (pintype "output"))
    )
    (net (code "147") (name "unconnected-(E22A-O5-Pad6)") (class "Default")
      (node (ref "E22") (pin "6") (pinfunction "O5_6") (pintype "output"))
    )
    (net (code "148") (name "unconnected-(E22A-O6-Pad7)") (class "Default")
      (node (ref "E22") (pin "7") (pinfunction "O6_7") (pintype "output"))
    )
    (net (code "149") (name "unconnected-(E22A-O7-Pad9)") (class "Default")
      (node (ref "E22") (pin "9") (pinfunction "O7_9") (pintype "output"))
    )
    (net (code "150") (name "unconnected-(E22A-O8-Pad10)") (class "Default")
      (node (ref "E22") (pin "10") (pinfunction "O8_10") (pintype "output"))
    )
    (net (code "151") (name "unconnected-(E22A-O9-Pad11)") (class "Default")
      (node (ref "E22") (pin "11") (pinfunction "O9_11") (pintype "output"))
    )
    (net (code "152") (name "unconnected-(E23B-~{Q}-Pad8)") (class "Default")
      (node (ref "E23") (pin "8") (pinfunction "~{Q}_8") (pintype "output"))
    )
    (net (code "153") (name "~{EXTPUL}") (class "Default")
      (node (ref "E10") (pin "2") (pinfunction "I1_2") (pintype "input"))
      (node (ref "J2") (pin "9") (pinfunction "9_9") (pintype "passive"))
      (node (ref "R4") (pin "2") (pinfunction "2_2") (pintype "passive"))
    )
    (net (code "154") (name "~{FUN}") (class "Default")
      (node (ref "E21") (pin "12") (pinfunction "I2_12") (pintype "input"))
      (node (ref "E21") (pin "13") (pinfunction "I3_13") (pintype "input"))
      (node (ref "E6") (pin "14") (pinfunction "GS_14") (pintype "output"))
      (node (ref "J2") (pin "15") (pinfunction "15_15") (pintype "passive"))
    )
    (net (code "155") (name "~{KEY-F}") (class "Default")
      (node (ref "E23") (pin "6") (pinfunction "~{Q}_6") (pintype "output"))
      (node (ref "J2") (pin "3") (pinfunction "3_3") (pintype "passive"))
    )
    (net (code "156") (name "~{KFUN0}") (class "Default")
      (node (ref "E10") (pin "11") (pinfunction "O_11") (pintype "output"))
      (node (ref "J1") (pin "3") (pinfunction "3_3") (pintype "passive"))
    )
    (net (code "157") (name "~{KFUN1}") (class "Default")
      (node (ref "E10") (pin "8") (pinfunction "O_8") (pintype "output"))
      (node (ref "J1") (pin "2") (pinfunction "2_2") (pintype "passive"))
    )
    (net (code "158") (name "~{KFUN2}") (class "Default")
      (node (ref "E10") (pin "6") (pinfunction "O_6") (pintype "output"))
      (node (ref "J1") (pin "1") (pinfunction "1_1") (pintype "passive"))
    )
    (net (code "159") (name "~{MCLOCK}") (class "Default")
      (node (ref "E10") (pin "3") (pinfunction "O_3") (pintype "output"))
      (node (ref "E20") (pin "3") (pinfunction "I_3") (pintype "input"))
      (node (ref "E24") (pin "9") (pinfunction "CK1_9") (pintype "input"))
      (node (ref "J2") (pin "1") (pinfunction "1_1") (pintype "passive"))
    )
    (net (code "160") (name "~{SHLT}") (class "Default")
      (node (ref "!SHLT") (pin "1") (pinfunction "S_1") (pintype "passive"))
      (node (ref "!SHLT") (pin "2") (pinfunction "S1_2") (pintype "passive"))
      (node (ref "E2") (pin "1") (pinfunction "I0_1") (pintype "input"))
      (node (ref "J1") (pin "5") (pinfunction "5_5") (pintype "passive"))
      (node (ref "R19") (pin "1") (pinfunction "1_1") (pintype "passive"))
    )
    (net (code "161") (name "~{STHIS}") (class "Default")
      (node (ref "E2") (pin "6") (pinfunction "O_6") (pintype "output"))
      (node (ref "J1") (pin "4") (pinfunction "4_4") (pintype "passive"))
    )
  )
)
